# AMR3350.net
KiCad netlist of a schematic drawn in EAGLE
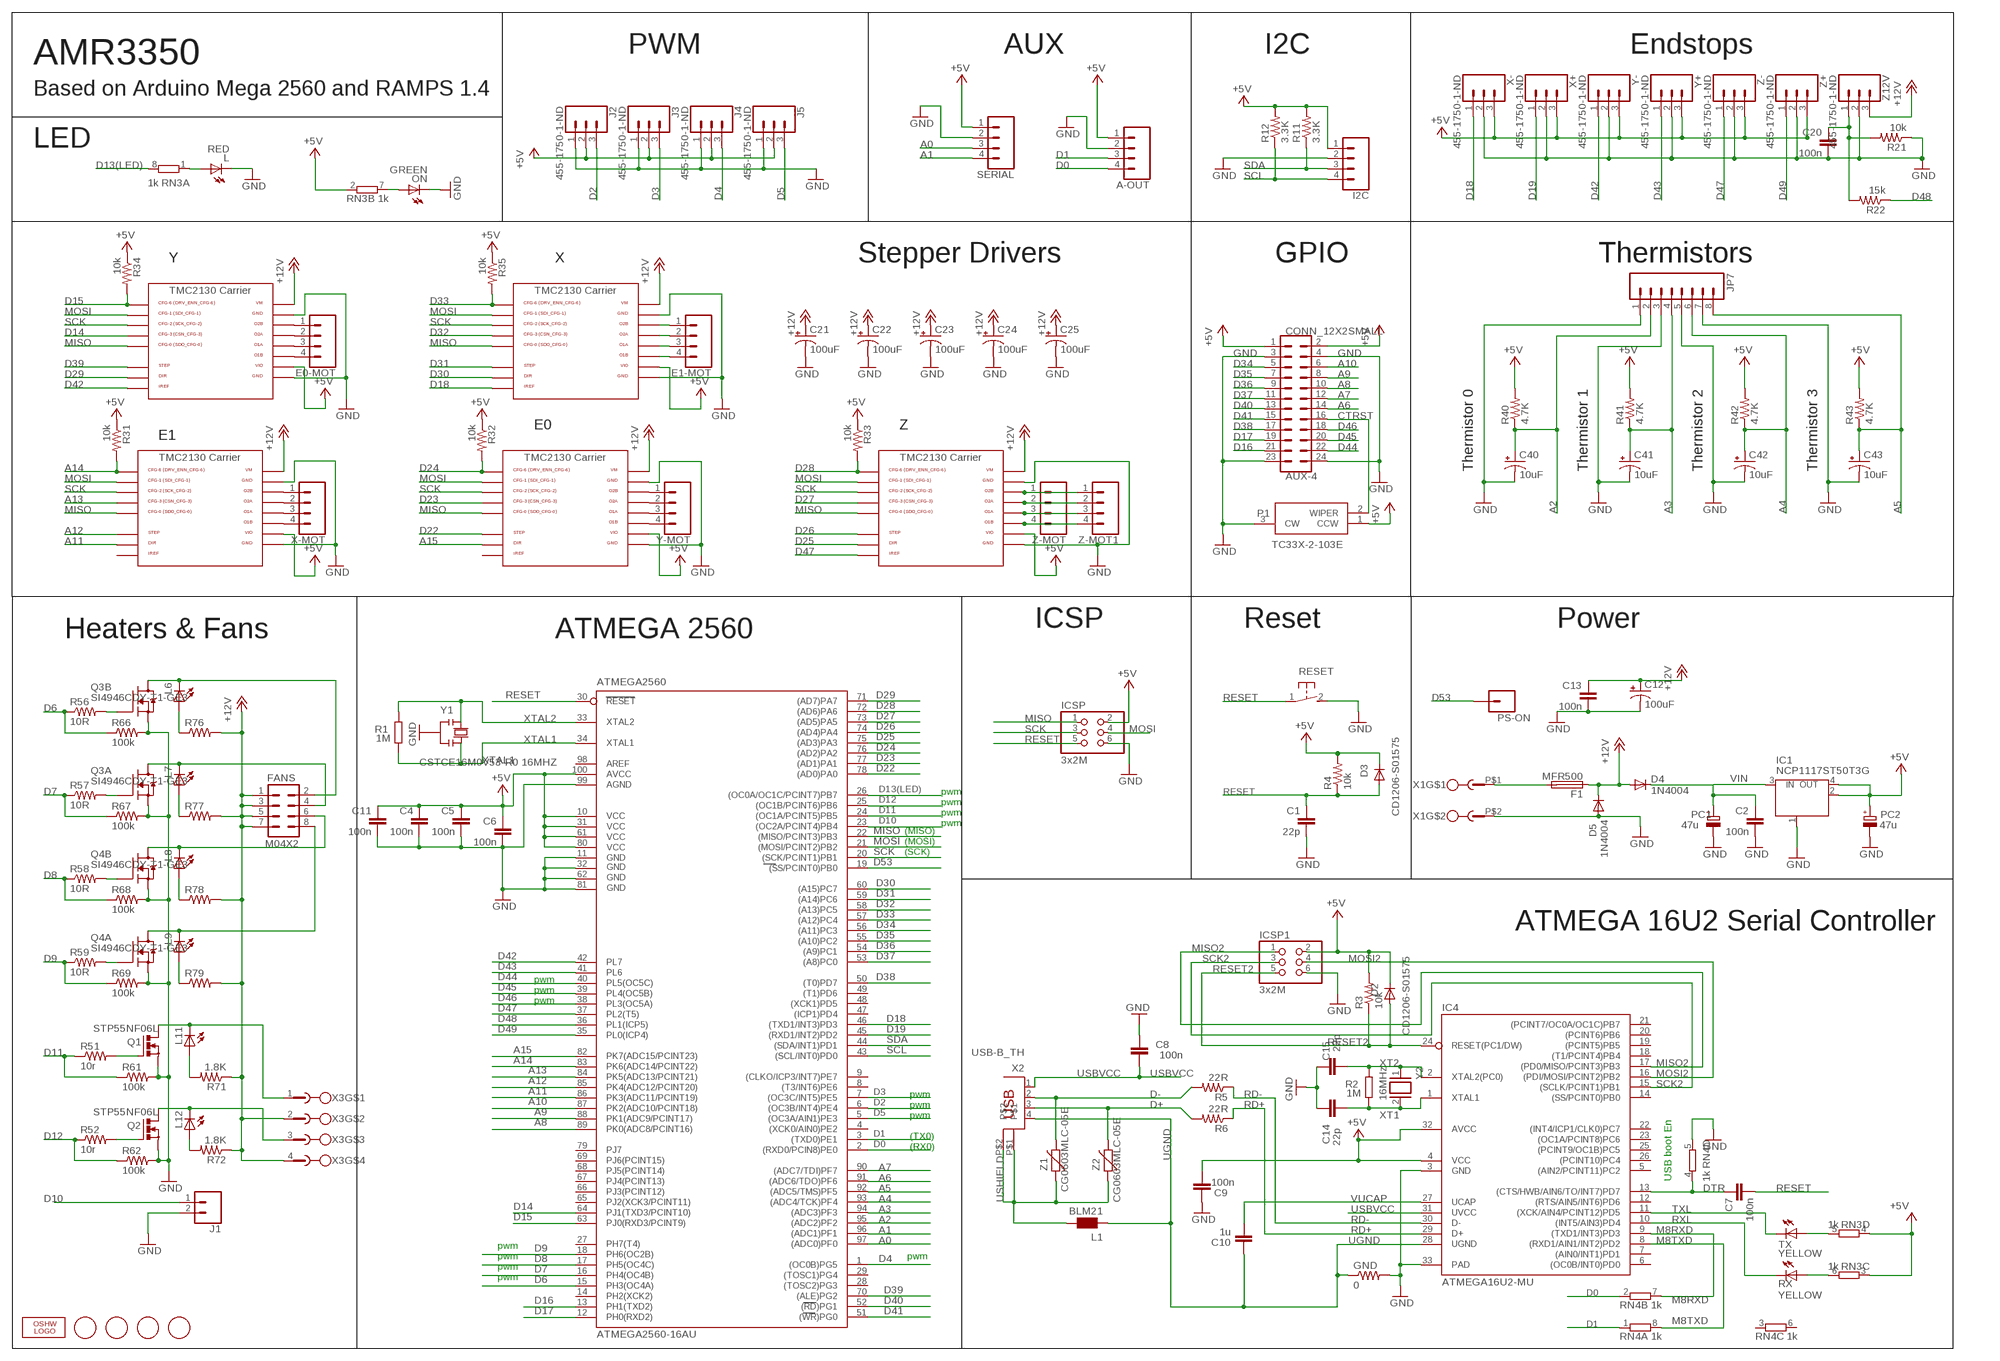
[diagram p0: schematic, sheet 1]

(export (version "E")
  (design (tool "Eeschema 10.0.6"))
  (components
    (comp (ref "A-OUT")
      (value "CONN_04SMALL")
      (footprint "eagle-import:1X04_SMALL")
      (libsource (lib "eagle-import") (part "CONN_04SMALL"))
    )
    (comp (ref "ATMEGA2560")
      (value "ATMEGA2560-16AU")
      (footprint "eagle-import:TQFP100")
      (libsource (lib "eagle-import") (part "ATMEGA2560AU2560-16"))
    )
    (comp (ref "AUX-4")
      (value "CONN_12X2SMALL")
      (footprint "eagle-import:2X12_SMALL")
      (libsource (lib "eagle-import") (part "CONN_12X2SMALL"))
    )
    (comp (ref "C1")
      (value "22p")
      (footprint "eagle-import:C0805RND")
      (libsource (lib "eagle-import") (part "C-EU"))
    )
    (comp (ref "C2")
      (value "100n")
      (footprint "eagle-import:C0805RND")
      (libsource (lib "eagle-import") (part "C-EU"))
    )
    (comp (ref "C4")
      (value "100n")
      (footprint "eagle-import:C0805RND")
      (libsource (lib "eagle-import") (part "C-EU"))
    )
    (comp (ref "C5")
      (value "100n")
      (footprint "eagle-import:C0805RND")
      (libsource (lib "eagle-import") (part "C-EU"))
    )
    (comp (ref "C6")
      (value "100n")
      (footprint "eagle-import:C0805RND")
      (libsource (lib "eagle-import") (part "C-EU"))
    )
    (comp (ref "C7")
      (value "100n")
      (footprint "eagle-import:C0805RND")
      (libsource (lib "eagle-import") (part "C-EU"))
    )
    (comp (ref "C8")
      (value "100n")
      (footprint "eagle-import:C0603-ROUND")
      (libsource (lib "eagle-import") (part "C-EU0603-RND"))
    )
    (comp (ref "C9")
      (value "100n")
      (footprint "eagle-import:C0603-ROUND")
      (libsource (lib "eagle-import") (part "C-EU0603-RND"))
    )
    (comp (ref "C10")
      (value "1u")
      (footprint "eagle-import:C0603-ROUND")
      (libsource (lib "eagle-import") (part "C-EU0603-RND"))
    )
    (comp (ref "C11")
      (value "100n")
      (footprint "eagle-import:C0603-ROUND")
      (libsource (lib "eagle-import") (part "C-EU0603-RND"))
    )
    (comp (ref "C12")
      (value "100uF")
      (footprint "eagle-import:153CLV-0605")
      (libsource (lib "eagle-import") (part "CPOL-US153CLV-0605"))
    )
    (comp (ref "C13")
      (value "100n")
      (footprint "eagle-import:C0805RND")
      (libsource (lib "eagle-import") (part "C-EU"))
    )
    (comp (ref "C14")
      (value "22p")
      (footprint "eagle-import:C0603-ROUND")
      (libsource (lib "eagle-import") (part "C-EU0603-RND"))
    )
    (comp (ref "C15")
      (value "22p")
      (footprint "eagle-import:C0603-ROUND")
      (libsource (lib "eagle-import") (part "C-EU0603-RND"))
    )
    (comp (ref "C20")
      (value "100n")
      (footprint "eagle-import:C0805RND")
      (libsource (lib "eagle-import") (part "C-EU"))
    )
    (comp (ref "C21")
      (value "100uF")
      (footprint "eagle-import:153CLV-0605")
      (libsource (lib "eagle-import") (part "CPOL-US153CLV-0605"))
    )
    (comp (ref "C22")
      (value "100uF")
      (footprint "eagle-import:153CLV-0605")
      (libsource (lib "eagle-import") (part "CPOL-US153CLV-0605"))
    )
    (comp (ref "C23")
      (value "100uF")
      (footprint "eagle-import:153CLV-0605")
      (libsource (lib "eagle-import") (part "CPOL-US153CLV-0605"))
    )
    (comp (ref "C24")
      (value "100uF")
      (footprint "eagle-import:153CLV-0605")
      (libsource (lib "eagle-import") (part "CPOL-US153CLV-0605"))
    )
    (comp (ref "C25")
      (value "100uF")
      (footprint "eagle-import:153CLV-0605")
      (libsource (lib "eagle-import") (part "CPOL-US153CLV-0605"))
    )
    (comp (ref "C40")
      (value "10uF")
      (footprint "eagle-import:153CLV-0405")
      (libsource (lib "eagle-import") (part "CPOL-US153CLV-0405"))
    )
    (comp (ref "C41")
      (value "10uF")
      (footprint "eagle-import:153CLV-0405")
      (libsource (lib "eagle-import") (part "CPOL-US153CLV-0405"))
    )
    (comp (ref "C42")
      (value "10uF")
      (footprint "eagle-import:153CLV-0405")
      (libsource (lib "eagle-import") (part "CPOL-US153CLV-0405"))
    )
    (comp (ref "C43")
      (value "10uF")
      (footprint "eagle-import:153CLV-0405")
      (libsource (lib "eagle-import") (part "CPOL-US153CLV-0405"))
    )
    (comp (ref "D2")
      (value "CD1206-S01575")
      (footprint "eagle-import:MINIMELF")
      (libsource (lib "eagle-import") (part "DIODE-MINIMELF"))
    )
    (comp (ref "D3")
      (value "CD1206-S01575")
      (footprint "eagle-import:MINIMELF")
      (libsource (lib "eagle-import") (part "DIODE-MINIMELF"))
    )
    (comp (ref "D4")
      (value "1N4004")
      (footprint "eagle-import:DO41-10")
      (libsource (lib "eagle-import") (part "1N4004"))
    )
    (comp (ref "D5")
      (value "1N4004")
      (footprint "eagle-import:DO41-10")
      (libsource (lib "eagle-import") (part "1N4004"))
    )
    (comp (ref "E0-MOT")
      (value "CONN_04SMALL")
      (footprint "eagle-import:1X04_SMALL")
      (libsource (lib "eagle-import") (part "CONN_04SMALL"))
    )
    (comp (ref "E1-MOT")
      (value "CONN_04SMALL")
      (footprint "eagle-import:1X04_SMALL")
      (libsource (lib "eagle-import") (part "CONN_04SMALL"))
    )
    (comp (ref "F1")
      (value "MFR500")
      (footprint "eagle-import:MFR500")
      (libsource (lib "eagle-import") (part "PTCFUSE"))
    )
    (comp (ref "FANS")
      (value "M04X2")
      (footprint "eagle-import:2X4")
      (libsource (lib "eagle-import") (part "M04X2"))
    )
    (comp (ref "FD1")
      (value "FIDUCIALMOUNT")
      (footprint "eagle-import:FIDUCIA-MOUNT")
      (libsource (lib "eagle-import") (part "FIDUCIALMOUNT"))
    )
    (comp (ref "FD2")
      (value "FIDUCIALMOUNT")
      (footprint "eagle-import:FIDUCIA-MOUNT")
      (libsource (lib "eagle-import") (part "FIDUCIALMOUNT"))
    )
    (comp (ref "FD3")
      (value "FIDUCIALMOUNT")
      (footprint "eagle-import:FIDUCIA-MOUNT")
      (libsource (lib "eagle-import") (part "FIDUCIALMOUNT"))
    )
    (comp (ref "FD4")
      (value "FIDUCIALMOUNT")
      (footprint "eagle-import:FIDUCIA-MOUNT")
      (libsource (lib "eagle-import") (part "FIDUCIALMOUNT"))
    )
    (comp (ref "GND")
      (value "0")
      (footprint "eagle-import:R0201")
      (libsource (lib "eagle-import") (part "R-US_R0201"))
    )
    (comp (ref "I2C")
      (value "CONN_04SMALL")
      (footprint "eagle-import:1X04_SMALL")
      (libsource (lib "eagle-import") (part "CONN_04SMALL"))
    )
    (comp (ref "IC1")
      (value "NCP1117ST50T3G")
      (footprint "eagle-import:SOT223")
      (libsource (lib "eagle-import") (part "MC33269ST-3.3T3"))
    )
    (comp (ref "IC4")
      (value "ATMEGA16U2-MU")
      (footprint "eagle-import:MLF32")
      (libsource (lib "eagle-import") (part "ATMEGA16U2-MU"))
    )
    (comp (ref "ICSP")
      (value "3x2M")
      (footprint "eagle-import:2X03")
      (libsource (lib "eagle-import") (part "PINHD-2X3"))
    )
    (comp (ref "ICSP1")
      (value "3x2M")
      (footprint "eagle-import:2X03")
      (libsource (lib "eagle-import") (part "PINHD-2X3"))
    )
    (comp (ref "J1")
      (value "CONN_02")
      (footprint "eagle-import:1X02")
      (libsource (lib "eagle-import") (part "CONN_02"))
    )
    (comp (ref "J2")
      (value "455-1750-1-ND")
      (footprint "eagle-import:1X03_SMALL")
      (libsource (lib "eagle-import") (part "CONN_03SMALL"))
    )
    (comp (ref "J3")
      (value "455-1750-1-ND")
      (footprint "eagle-import:1X03_SMALL")
      (libsource (lib "eagle-import") (part "CONN_03SMALL"))
    )
    (comp (ref "J4")
      (value "455-1750-1-ND")
      (footprint "eagle-import:1X03_SMALL")
      (libsource (lib "eagle-import") (part "CONN_03SMALL"))
    )
    (comp (ref "J5")
      (value "455-1750-1-ND")
      (footprint "eagle-import:1X03_SMALL")
      (libsource (lib "eagle-import") (part "CONN_03SMALL"))
    )
    (comp (ref "JP7")
      (value "CONN_08")
      (footprint "eagle-import:1X08_SMALL")
      (libsource (lib "eagle-import") (part "CONN_08"))
    )
    (comp (ref "L")
      (value "RED")
      (footprint "eagle-import:CHIP-LED0805")
      (libsource (lib "eagle-import") (part "LEDCHIP-LED0805"))
    )
    (comp (ref "L1")
      (value "BLM21")
      (footprint "eagle-import:0805")
      (libsource (lib "eagle-import") (part "WE-CBF_0805"))
    )
    (comp (ref "L6")
      (value "LEDCHIP-LED0603")
      (footprint "eagle-import:CHIP-LED0603")
      (libsource (lib "eagle-import") (part "LEDCHIP-LED0603"))
    )
    (comp (ref "L7")
      (value "LEDCHIP-LED0603")
      (footprint "eagle-import:CHIP-LED0603")
      (libsource (lib "eagle-import") (part "LEDCHIP-LED0603"))
    )
    (comp (ref "L8")
      (value "LEDCHIP-LED0603")
      (footprint "eagle-import:CHIP-LED0603")
      (libsource (lib "eagle-import") (part "LEDCHIP-LED0603"))
    )
    (comp (ref "L9")
      (value "LEDCHIP-LED0603")
      (footprint "eagle-import:CHIP-LED0603")
      (libsource (lib "eagle-import") (part "LEDCHIP-LED0603"))
    )
    (comp (ref "L11")
      (value "LEDCHIP-LED0805")
      (footprint "eagle-import:CHIP-LED0805")
      (libsource (lib "eagle-import") (part "LEDCHIP-LED0805"))
    )
    (comp (ref "L12")
      (value "LEDCHIP-LED0805")
      (footprint "eagle-import:CHIP-LED0805")
      (libsource (lib "eagle-import") (part "LEDCHIP-LED0805"))
    )
    (comp (ref "LOGO2")
      (value "OSHW_LOGO_6MILX0100-NT")
      (footprint "eagle-import:OSHW_6X100_NOTEXT")
      (libsource (lib "eagle-import") (part "OSHW_LOGO_6MILX0100-NT"))
    )
    (comp (ref "ON")
      (value "GREEN")
      (footprint "eagle-import:CHIP-LED0805")
      (libsource (lib "eagle-import") (part "LEDCHIP-LED0805"))
    )
    (comp (ref "P1")
      (value "TC33X-2-103E")
      (footprint "eagle-import:TC33X-2_1")
      (fields (field (name "RS_PART_NUMBER") "1673549"))
      (libsource (lib "eagle-import") (part "TC33X-2-103E"))
    )
    (comp (ref "PC1")
      (value "47u")
      (footprint "eagle-import:PANASONIC_D")
      (libsource (lib "eagle-import") (part "CPOL-EUD"))
    )
    (comp (ref "PC2")
      (value "47u")
      (footprint "eagle-import:PANASONIC_D")
      (libsource (lib "eagle-import") (part "CPOL-EUD"))
    )
    (comp (ref "PS-ON")
      (value "CONN_01SMALL")
      (footprint "eagle-import:1X01_SMALL")
      (libsource (lib "eagle-import") (part "CONN_01SMALL"))
    )
    (comp (ref "Q1")
      (value "STP55NF06L")
      (footprint "eagle-import:TO220BV")
      (libsource (lib "eagle-import") (part "IRF512"))
    )
    (comp (ref "Q2")
      (value "STP55NF06L")
      (footprint "eagle-import:TO220BV")
      (libsource (lib "eagle-import") (part "IRF512"))
    )
    (comp (ref "Q3")
      (value "SI4946CDY-T1-GE3")
      (footprint "eagle-import:SOIC127P600X175-8N")
      (libsource (lib "eagle-import") (part "SI4946CDY-T1-GE3"))
    )
    (comp (ref "Q4")
      (value "SI4946CDY-T1-GE3")
      (footprint "eagle-import:SOIC127P600X175-8N")
      (libsource (lib "eagle-import") (part "SI4946CDY-T1-GE3"))
    )
    (comp (ref "R1")
      (value "1M")
      (footprint "eagle-import:R0805RND")
      (libsource (lib "eagle-import") (part "R-EU_"))
    )
    (comp (ref "R2")
      (value "1M")
      (footprint "eagle-import:R0603-ROUND")
      (libsource (lib "eagle-import") (part "R-EU_R0603"))
    )
    (comp (ref "R3")
      (value "10k")
      (footprint "eagle-import:R0805")
      (libsource (lib "eagle-import") (part "resistor_348_R-US_R0805"))
    )
    (comp (ref "R4")
      (value "10k")
      (footprint "eagle-import:R0805")
      (libsource (lib "eagle-import") (part "resistor_348_R-US_R0805"))
    )
    (comp (ref "R5")
      (value "22R")
      (footprint "eagle-import:R0603")
      (libsource (lib "eagle-import") (part "resistor_348_R-US_R0603"))
    )
    (comp (ref "R6")
      (value "22R")
      (footprint "eagle-import:R0603")
      (libsource (lib "eagle-import") (part "resistor_348_R-US_R0603"))
    )
    (comp (ref "R11")
      (value "3.3K")
      (footprint "eagle-import:R0805")
      (libsource (lib "eagle-import") (part "R-US_R0805"))
    )
    (comp (ref "R12")
      (value "3.3K")
      (footprint "eagle-import:R0805")
      (libsource (lib "eagle-import") (part "R-US_R0805"))
    )
    (comp (ref "R21")
      (value "10k")
      (footprint "eagle-import:R0805")
      (libsource (lib "eagle-import") (part "R-US_R0805"))
    )
    (comp (ref "R22")
      (value "15k")
      (footprint "eagle-import:R0805")
      (libsource (lib "eagle-import") (part "R-US_R0805"))
    )
    (comp (ref "R31")
      (value "10k")
      (footprint "eagle-import:R0805")
      (libsource (lib "eagle-import") (part "R-US_R0805"))
    )
    (comp (ref "R32")
      (value "10k")
      (footprint "eagle-import:R0805")
      (libsource (lib "eagle-import") (part "R-US_R0805"))
    )
    (comp (ref "R33")
      (value "10k")
      (footprint "eagle-import:R0805")
      (libsource (lib "eagle-import") (part "R-US_R0805"))
    )
    (comp (ref "R34")
      (value "10k")
      (footprint "eagle-import:R0805")
      (libsource (lib "eagle-import") (part "R-US_R0805"))
    )
    (comp (ref "R35")
      (value "10k")
      (footprint "eagle-import:R0805")
      (libsource (lib "eagle-import") (part "R-US_R0805"))
    )
    (comp (ref "R40")
      (value "4.7K")
      (footprint "eagle-import:R0805")
      (libsource (lib "eagle-import") (part "R-US_R0805"))
    )
    (comp (ref "R41")
      (value "4.7K")
      (footprint "eagle-import:R0805")
      (libsource (lib "eagle-import") (part "R-US_R0805"))
    )
    (comp (ref "R42")
      (value "4.7K")
      (footprint "eagle-import:R0805")
      (libsource (lib "eagle-import") (part "R-US_R0805"))
    )
    (comp (ref "R43")
      (value "4.7K")
      (footprint "eagle-import:R0805")
      (libsource (lib "eagle-import") (part "R-US_R0805"))
    )
    (comp (ref "R51")
      (value "10r")
      (footprint "eagle-import:R0805")
      (libsource (lib "eagle-import") (part "resistor_R-US_R0805"))
    )
    (comp (ref "R52")
      (value "10r")
      (footprint "eagle-import:M0805")
      (libsource (lib "eagle-import") (part "resistor_R-US_M0805"))
    )
    (comp (ref "R56")
      (value "10R")
      (footprint "eagle-import:R0805")
      (libsource (lib "eagle-import") (part "resistor_348_R-US_R0805"))
    )
    (comp (ref "R57")
      (value "10R")
      (footprint "eagle-import:R0805")
      (libsource (lib "eagle-import") (part "resistor_348_R-US_R0805"))
    )
    (comp (ref "R58")
      (value "10R")
      (footprint "eagle-import:R0805")
      (libsource (lib "eagle-import") (part "resistor_348_R-US_R0805"))
    )
    (comp (ref "R59")
      (value "10R")
      (footprint "eagle-import:R0805")
      (libsource (lib "eagle-import") (part "resistor_348_R-US_R0805"))
    )
    (comp (ref "R61")
      (value "100k")
      (footprint "eagle-import:R0805")
      (libsource (lib "eagle-import") (part "R-US_R0805"))
    )
    (comp (ref "R62")
      (value "100k")
      (footprint "eagle-import:R0805")
      (libsource (lib "eagle-import") (part "R-US_R0805"))
    )
    (comp (ref "R66")
      (value "100k")
      (footprint "eagle-import:R0805")
      (libsource (lib "eagle-import") (part "resistor_348_R-US_R0805"))
    )
    (comp (ref "R67")
      (value "100k")
      (footprint "eagle-import:R0805")
      (libsource (lib "eagle-import") (part "resistor_348_R-US_R0805"))
    )
    (comp (ref "R68")
      (value "100k")
      (footprint "eagle-import:R0805")
      (libsource (lib "eagle-import") (part "resistor_348_R-US_R0805"))
    )
    (comp (ref "R69")
      (value "100k")
      (footprint "eagle-import:R0805")
      (libsource (lib "eagle-import") (part "resistor_348_R-US_R0805"))
    )
    (comp (ref "R71")
      (value "1.8K")
      (footprint "eagle-import:R0805")
      (libsource (lib "eagle-import") (part "R-US_R0805"))
    )
    (comp (ref "R72")
      (value "1.8K")
      (footprint "eagle-import:R0805")
      (libsource (lib "eagle-import") (part "R-US_R0805"))
    )
    (comp (ref "R76")
      (value "R-US_R0603")
      (footprint "eagle-import:R0603")
      (libsource (lib "eagle-import") (part "resistor_348_R-US_R0603"))
    )
    (comp (ref "R77")
      (value "R-US_R0603")
      (footprint "eagle-import:R0603")
      (libsource (lib "eagle-import") (part "resistor_348_R-US_R0603"))
    )
    (comp (ref "R78")
      (value "R-US_R0603")
      (footprint "eagle-import:R0603")
      (libsource (lib "eagle-import") (part "resistor_348_R-US_R0603"))
    )
    (comp (ref "R79")
      (value "R-US_R0603")
      (footprint "eagle-import:R0603")
      (libsource (lib "eagle-import") (part "resistor_348_R-US_R0603"))
    )
    (comp (ref "RESET")
      (value "31-XX")
      (footprint "eagle-import:B3F-31XX")
      (fields (field (name "MPN") "B3F-3100"))
      (libsource (lib "eagle-import") (part "31-XX"))
    )
    (comp (ref "RN3")
      (value "1k")
      (footprint "eagle-import:CAY16")
      (libsource (lib "eagle-import") (part "4R-NCAY16"))
    )
    (comp (ref "RN4")
      (value "1k")
      (footprint "eagle-import:CAY16")
      (libsource (lib "eagle-import") (part "4R-NCAY16"))
    )
    (comp (ref "RX")
      (value "YELLOW")
      (footprint "eagle-import:CHIP-LED0805")
      (libsource (lib "eagle-import") (part "LEDCHIP-LED0805"))
    )
    (comp (ref "SERIAL")
      (value "CONN_04SMALL")
      (footprint "eagle-import:1X04_SMALL")
      (libsource (lib "eagle-import") (part "CONN_04SMALL"))
    )
    (comp (ref "TX")
      (value "YELLOW")
      (footprint "eagle-import:CHIP-LED0805")
      (libsource (lib "eagle-import") (part "LEDCHIP-LED0805"))
    )
    (comp (ref "U$1")
      (value "TMC2130BREAKOUT")
      (footprint "eagle-import:TMC2130BREAKOUT")
      (libsource (lib "eagle-import") (part "TMC2130BREAKOUT"))
    )
    (comp (ref "U$2")
      (value "TMC2130BREAKOUT")
      (footprint "eagle-import:TMC2130BREAKOUT")
      (libsource (lib "eagle-import") (part "TMC2130BREAKOUT"))
    )
    (comp (ref "U$3")
      (value "TMC2130BREAKOUT")
      (footprint "eagle-import:TMC2130BREAKOUT")
      (libsource (lib "eagle-import") (part "TMC2130BREAKOUT"))
    )
    (comp (ref "U$4")
      (value "TMC2130BREAKOUT")
      (footprint "eagle-import:TMC2130BREAKOUT")
      (libsource (lib "eagle-import") (part "TMC2130BREAKOUT"))
    )
    (comp (ref "U$5")
      (value "TMC2130BREAKOUT")
      (footprint "eagle-import:TMC2130BREAKOUT")
      (libsource (lib "eagle-import") (part "TMC2130BREAKOUT"))
    )
    (comp (ref "X+")
      (value "455-1750-1-ND")
      (footprint "eagle-import:1X03_SMALL")
      (libsource (lib "eagle-import") (part "CONN_03SMALL"))
    )
    (comp (ref "X-")
      (value "455-1750-1-ND")
      (footprint "eagle-import:1X03_SMALL")
      (libsource (lib "eagle-import") (part "CONN_03SMALL"))
    )
    (comp (ref "X-MOT")
      (value "CONN_04SMALL")
      (footprint "eagle-import:1X04_SMALL")
      (libsource (lib "eagle-import") (part "CONN_04SMALL"))
    )
    (comp (ref "X1")
      (value "XT60")
      (footprint "eagle-import:XT60")
      (libsource (lib "eagle-import") (part "XT60"))
    )
    (comp (ref "X2")
      (value "USB-B_TH")
      (footprint "eagle-import:PN61729-NOSILK")
      (libsource (lib "eagle-import") (part "PN61729NOSILK"))
    )
    (comp (ref "X3")
      (value "4-PIN")
      (footprint "eagle-import:4-PIN")
      (libsource (lib "eagle-import") (part "4-PIN"))
    )
    (comp (ref "Y+")
      (value "455-1750-1-ND")
      (footprint "eagle-import:1X03_SMALL")
      (libsource (lib "eagle-import") (part "CONN_03SMALL"))
    )
    (comp (ref "Y-")
      (value "455-1750-1-ND")
      (footprint "eagle-import:1X03_SMALL")
      (libsource (lib "eagle-import") (part "CONN_03SMALL"))
    )
    (comp (ref "Y-MOT")
      (value "CONN_04SMALL")
      (footprint "eagle-import:1X04_SMALL")
      (libsource (lib "eagle-import") (part "CONN_04SMALL"))
    )
    (comp (ref "Y1")
      (value "CSTCE16M0V53-R0 16MHZ")
      (footprint "eagle-import:RESONATOR")
      (libsource (lib "eagle-import") (part "RESONATORMU"))
    )
    (comp (ref "Y2")
      (value "16MHz")
      (footprint "eagle-import:QS")
      (libsource (lib "eagle-import") (part "XTAL/S"))
    )
    (comp (ref "Z+")
      (value "455-1750-1-ND")
      (footprint "eagle-import:1X03_SMALL")
      (libsource (lib "eagle-import") (part "CONN_03SMALL"))
    )
    (comp (ref "Z-")
      (value "455-1750-1-ND")
      (footprint "eagle-import:1X03_SMALL")
      (libsource (lib "eagle-import") (part "CONN_03SMALL"))
    )
    (comp (ref "Z-MOT")
      (value "CONN_04SMALL")
      (footprint "eagle-import:1X04_SMALL")
      (libsource (lib "eagle-import") (part "CONN_04SMALL"))
    )
    (comp (ref "Z-MOT1")
      (value "CONN_04SMALL")
      (footprint "eagle-import:1X04_SMALL")
      (libsource (lib "eagle-import") (part "CONN_04SMALL"))
    )
    (comp (ref "Z1")
      (value "CG0603MLC-05E")
      (footprint "eagle-import:CT_CN0603")
      (libsource (lib "eagle-import") (part "VARISTORCN0603"))
    )
    (comp (ref "Z2")
      (value "CG0603MLC-05E")
      (footprint "eagle-import:CT_CN0603")
      (libsource (lib "eagle-import") (part "VARISTORCN0603"))
    )
    (comp (ref "Z12V")
      (value "455-1750-1-ND")
      (footprint "eagle-import:1X03_SMALL")
      (libsource (lib "eagle-import") (part "CONN_03SMALL"))
    )
  )
  (nets
    (net (code "1") (name "+5V") (class "Default")
      (node (ref "A-OUT") (pin "1") (pinfunction "1_1") (pintype "passive"))
      (node (ref "ATMEGA2560") (pin "10") (pinfunction "VCC_10") (pintype "power_in"))
      (node (ref "ATMEGA2560") (pin "100") (pinfunction "AVCC_100") (pintype "power_in"))
      (node (ref "ATMEGA2560") (pin "31") (pinfunction "VCC1_31") (pintype "power_in"))
      (node (ref "ATMEGA2560") (pin "61") (pinfunction "VCC2_61") (pintype "power_in"))
      (node (ref "ATMEGA2560") (pin "80") (pinfunction "VCC3_80") (pintype "power_in"))
      (node (ref "AUX-4") (pin "1") (pinfunction "1_1") (pintype "passive"))
      (node (ref "AUX-4") (pin "2") (pinfunction "2_2") (pintype "passive"))
      (node (ref "C11") (pin "1") (pinfunction "1_1") (pintype "passive"))
      (node (ref "C4") (pin "1") (pinfunction "1_1") (pintype "passive"))
      (node (ref "C5") (pin "1") (pinfunction "1_1") (pintype "passive"))
      (node (ref "C6") (pin "1") (pinfunction "1_1") (pintype "passive"))
      (node (ref "C9") (pin "1") (pinfunction "1_1") (pintype "passive"))
      (node (ref "D2") (pin "C") (pinfunction "C_C") (pintype "passive"))
      (node (ref "D3") (pin "C") (pinfunction "C_C") (pintype "passive"))
      (node (ref "I2C") (pin "1") (pinfunction "1_1") (pintype "passive"))
      (node (ref "IC1") (pin "2") (pinfunction "OUT_2") (pintype "passive"))
      (node (ref "IC1") (pin "4") (pinfunction "OUT_4") (pintype "passive"))
      (node (ref "IC4") (pin "32") (pinfunction "AVCC_32") (pintype "power_in"))
      (node (ref "IC4") (pin "4") (pinfunction "VCC_4") (pintype "power_in"))
      (node (ref "ICSP") (pin "2") (pinfunction "2_2") (pintype "passive"))
      (node (ref "ICSP1") (pin "2") (pinfunction "2_2") (pintype "passive"))
      (node (ref "J2") (pin "2") (pinfunction "2_2") (pintype "passive"))
      (node (ref "J3") (pin "2") (pinfunction "2_2") (pintype "passive"))
      (node (ref "J4") (pin "2") (pinfunction "2_2") (pintype "passive"))
      (node (ref "J5") (pin "2") (pinfunction "2_2") (pintype "passive"))
      (node (ref "P1") (pin "1") (pinfunction "CCW_1") (pintype "bidirectional"))
      (node (ref "PC2") (pin "+") (pinfunction "+_+") (pintype "passive"))
      (node (ref "R11") (pin "2") (pinfunction "2_2") (pintype "passive"))
      (node (ref "R12") (pin "2") (pinfunction "2_2") (pintype "passive"))
      (node (ref "R3") (pin "2") (pinfunction "2_2") (pintype "passive"))
      (node (ref "R31") (pin "1") (pinfunction "1_1") (pintype "passive"))
      (node (ref "R32") (pin "1") (pinfunction "1_1") (pintype "passive"))
      (node (ref "R33") (pin "1") (pinfunction "1_1") (pintype "passive"))
      (node (ref "R34") (pin "1") (pinfunction "1_1") (pintype "passive"))
      (node (ref "R35") (pin "1") (pinfunction "1_1") (pintype "passive"))
      (node (ref "R4") (pin "2") (pinfunction "2_2") (pintype "passive"))
      (node (ref "R40") (pin "2") (pinfunction "2_2") (pintype "passive"))
      (node (ref "R41") (pin "2") (pinfunction "2_2") (pintype "passive"))
      (node (ref "R42") (pin "2") (pinfunction "2_2") (pintype "passive"))
      (node (ref "R43") (pin "2") (pinfunction "2_2") (pintype "passive"))
      (node (ref "RN3") (pin "2") (pinfunction "1_2") (pintype "passive"))
      (node (ref "RN3") (pin "3") (pinfunction "1_3") (pintype "passive"))
      (node (ref "RN3") (pin "4") (pinfunction "1_4") (pintype "passive"))
      (node (ref "SERIAL") (pin "1") (pinfunction "1_1") (pintype "passive"))
      (node (ref "U$1") (pin "VIO") (pinfunction "VIO_VIO") (pintype "power_in"))
      (node (ref "U$2") (pin "VIO") (pinfunction "VIO_VIO") (pintype "power_in"))
      (node (ref "U$3") (pin "VIO") (pinfunction "VIO_VIO") (pintype "power_in"))
      (node (ref "U$4") (pin "VIO") (pinfunction "VIO_VIO") (pintype "power_in"))
      (node (ref "U$5") (pin "VIO") (pinfunction "VIO_VIO") (pintype "power_in"))
      (node (ref "X+") (pin "3") (pinfunction "3_3") (pintype "passive"))
      (node (ref "X-") (pin "3") (pinfunction "3_3") (pintype "passive"))
      (node (ref "Y+") (pin "3") (pinfunction "3_3") (pintype "passive"))
      (node (ref "Y-") (pin "3") (pinfunction "3_3") (pintype "passive"))
      (node (ref "Z+") (pin "3") (pinfunction "3_3") (pintype "passive"))
      (node (ref "Z-") (pin "3") (pinfunction "3_3") (pintype "passive"))
    )
    (net (code "2") (name "+12V") (class "Default")
      (node (ref "C12") (pin "+") (pinfunction "+_+") (pintype "passive"))
      (node (ref "C13") (pin "1") (pinfunction "1_1") (pintype "passive"))
      (node (ref "C21") (pin "+") (pinfunction "+_+") (pintype "passive"))
      (node (ref "C22") (pin "+") (pinfunction "+_+") (pintype "passive"))
      (node (ref "C23") (pin "+") (pinfunction "+_+") (pintype "passive"))
      (node (ref "C24") (pin "+") (pinfunction "+_+") (pintype "passive"))
      (node (ref "C25") (pin "+") (pinfunction "+_+") (pintype "passive"))
      (node (ref "D4") (pin "A") (pinfunction "A_A") (pintype "passive"))
      (node (ref "D5") (pin "C") (pinfunction "C_C") (pintype "passive"))
      (node (ref "F1") (pin "1") (pinfunction "1_1") (pintype "passive"))
      (node (ref "FANS") (pin "1") (pinfunction "1_1") (pintype "passive"))
      (node (ref "FANS") (pin "3") (pinfunction "3_3") (pintype "passive"))
      (node (ref "FANS") (pin "5") (pinfunction "5_5") (pintype "passive"))
      (node (ref "FANS") (pin "7") (pinfunction "7_7") (pintype "passive"))
      (node (ref "R71") (pin "1") (pinfunction "1_1") (pintype "passive"))
      (node (ref "R72") (pin "1") (pinfunction "1_1") (pintype "passive"))
      (node (ref "R76") (pin "2") (pinfunction "2_2") (pintype "passive"))
      (node (ref "R77") (pin "2") (pinfunction "2_2") (pintype "passive"))
      (node (ref "R78") (pin "2") (pinfunction "2_2") (pintype "passive"))
      (node (ref "R79") (pin "2") (pinfunction "2_2") (pintype "passive"))
      (node (ref "U$1") (pin "VM") (pinfunction "VM_VM") (pintype "power_in"))
      (node (ref "U$2") (pin "VM") (pinfunction "VM_VM") (pintype "power_in"))
      (node (ref "U$3") (pin "VM") (pinfunction "VM_VM") (pintype "power_in"))
      (node (ref "U$4") (pin "VM") (pinfunction "VM_VM") (pintype "power_in"))
      (node (ref "U$5") (pin "VM") (pinfunction "VM_VM") (pintype "power_in"))
      (node (ref "X3") (pin "2") (pinfunction "1_2") (pintype "passive"))
      (node (ref "X3") (pin "4") (pinfunction "1_4") (pintype "passive"))
      (node (ref "Z12V") (pin "3") (pinfunction "3_3") (pintype "passive"))
    )
    (net (code "3") (name "/A0") (class "Default")
      (node (ref "ATMEGA2560") (pin "97") (pinfunction "(ADC0)PF0_97") (pintype "bidirectional"))
      (node (ref "SERIAL") (pin "3") (pinfunction "3_3") (pintype "passive"))
    )
    (net (code "4") (name "/A1") (class "Default")
      (node (ref "ATMEGA2560") (pin "96") (pinfunction "(ADC1)PF1_96") (pintype "bidirectional"))
      (node (ref "SERIAL") (pin "4") (pinfunction "4_4") (pintype "passive"))
    )
    (net (code "5") (name "/A2") (class "Default")
      (node (ref "ATMEGA2560") (pin "95") (pinfunction "(ADC2)PF2_95") (pintype "bidirectional"))
      (node (ref "C40") (pin "+") (pinfunction "+_+") (pintype "passive"))
      (node (ref "JP7") (pin "2") (pinfunction "2_2") (pintype "passive"))
      (node (ref "R40") (pin "1") (pinfunction "1_1") (pintype "passive"))
    )
    (net (code "6") (name "/A3") (class "Default")
      (node (ref "ATMEGA2560") (pin "94") (pinfunction "(ADC3)PF3_94") (pintype "bidirectional"))
      (node (ref "C41") (pin "+") (pinfunction "+_+") (pintype "passive"))
      (node (ref "JP7") (pin "4") (pinfunction "4_4") (pintype "passive"))
      (node (ref "R41") (pin "1") (pinfunction "1_1") (pintype "passive"))
    )
    (net (code "7") (name "/A4") (class "Default")
      (node (ref "ATMEGA2560") (pin "93") (pinfunction "(ADC4/TCK)PF4_93") (pintype "bidirectional"))
      (node (ref "C42") (pin "+") (pinfunction "+_+") (pintype "passive"))
      (node (ref "JP7") (pin "6") (pinfunction "6_6") (pintype "passive"))
      (node (ref "R42") (pin "1") (pinfunction "1_1") (pintype "passive"))
    )
    (net (code "8") (name "/A5") (class "Default")
      (node (ref "ATMEGA2560") (pin "92") (pinfunction "(ADC5/TMS)PF5_92") (pintype "bidirectional"))
      (node (ref "C43") (pin "+") (pinfunction "+_+") (pintype "passive"))
      (node (ref "JP7") (pin "8") (pinfunction "8_8") (pintype "passive"))
      (node (ref "R43") (pin "1") (pinfunction "1_1") (pintype "passive"))
    )
    (net (code "9") (name "/A6") (class "Default")
      (node (ref "ATMEGA2560") (pin "91") (pinfunction "(ADC6/TDO)PF6_91") (pintype "bidirectional"))
      (node (ref "AUX-4") (pin "14") (pinfunction "14_14") (pintype "passive"))
    )
    (net (code "10") (name "/A7") (class "Default")
      (node (ref "ATMEGA2560") (pin "90") (pinfunction "(ADC7/TDI)PF7_90") (pintype "bidirectional"))
      (node (ref "AUX-4") (pin "12") (pinfunction "12_12") (pintype "passive"))
    )
    (net (code "11") (name "/A8") (class "Default")
      (node (ref "ATMEGA2560") (pin "89") (pinfunction "PK0(ADC8/PCINT16)_89") (pintype "bidirectional"))
      (node (ref "AUX-4") (pin "10") (pinfunction "10_10") (pintype "passive"))
    )
    (net (code "12") (name "/A9") (class "Default")
      (node (ref "ATMEGA2560") (pin "88") (pinfunction "PK1(ADC9/PCINT17)_88") (pintype "bidirectional"))
      (node (ref "AUX-4") (pin "8") (pinfunction "8_8") (pintype "passive"))
    )
    (net (code "13") (name "/A10") (class "Default")
      (node (ref "ATMEGA2560") (pin "87") (pinfunction "PK2(ADC10/PCINT18)_87") (pintype "bidirectional"))
      (node (ref "AUX-4") (pin "6") (pinfunction "6_6") (pintype "passive"))
    )
    (net (code "14") (name "/A11") (class "Default")
      (node (ref "ATMEGA2560") (pin "86") (pinfunction "PK3(ADC11/PCINT19)_86") (pintype "bidirectional"))
      (node (ref "U$1") (pin "DIR") (pinfunction "DIR_DIR") (pintype "input"))
    )
    (net (code "15") (name "/A12") (class "Default")
      (node (ref "ATMEGA2560") (pin "85") (pinfunction "PK4(ADC12/PCINT20)_85") (pintype "bidirectional"))
      (node (ref "U$1") (pin "STEP") (pinfunction "STEP_STEP") (pintype "input"))
    )
    (net (code "16") (name "/A13") (class "Default")
      (node (ref "ATMEGA2560") (pin "84") (pinfunction "PK5(ADC13/PCINT21)_84") (pintype "bidirectional"))
      (node (ref "U$1") (pin "CFG-3") (pinfunction "CFG-3_CFG-3") (pintype "bidirectional"))
    )
    (net (code "17") (name "/A14") (class "Default")
      (node (ref "ATMEGA2560") (pin "83") (pinfunction "PK6(ADC14/PCINT22)_83") (pintype "bidirectional"))
      (node (ref "R31") (pin "2") (pinfunction "2_2") (pintype "passive"))
      (node (ref "U$1") (pin "CFG-6") (pinfunction "CFG-6_CFG-6") (pintype "bidirectional"))
    )
    (net (code "18") (name "/A15") (class "Default")
      (node (ref "ATMEGA2560") (pin "82") (pinfunction "PK7(ADC15/PCINT23)_82") (pintype "bidirectional"))
      (node (ref "U$2") (pin "DIR") (pinfunction "DIR_DIR") (pintype "input"))
    )
    (net (code "19") (name "/CTRST") (class "Default")
      (node (ref "AUX-4") (pin "16") (pinfunction "16_16") (pintype "passive"))
      (node (ref "P1") (pin "2") (pinfunction "WIPER_2") (pintype "bidirectional"))
    )
    (net (code "20") (name "/D+") (class "Default")
      (node (ref "R6") (pin "2") (pinfunction "2_2") (pintype "passive"))
      (node (ref "X2") (pin "3") (pinfunction "3_3") (pintype "bidirectional"))
      (node (ref "Z2") (pin "2") (pinfunction "2_2") (pintype "passive"))
    )
    (net (code "21") (name "/D-") (class "Default")
      (node (ref "R5") (pin "2") (pinfunction "2_2") (pintype "passive"))
      (node (ref "X2") (pin "2") (pinfunction "2_2") (pintype "bidirectional"))
      (node (ref "Z1") (pin "2") (pinfunction "2_2") (pintype "passive"))
    )
    (net (code "22") (name "/D0") (class "Default")
      (node (ref "A-OUT") (pin "4") (pinfunction "4_4") (pintype "passive"))
      (node (ref "ATMEGA2560") (pin "2") (pinfunction "(RXD0/PCIN8)PE0_2") (pintype "bidirectional"))
      (node (ref "RN4") (pin "2") (pinfunction "1_2") (pintype "passive"))
    )
    (net (code "23") (name "/D1") (class "Default")
      (node (ref "A-OUT") (pin "3") (pinfunction "3_3") (pintype "passive"))
      (node (ref "ATMEGA2560") (pin "3") (pinfunction "(TXD0)PE1_3") (pintype "bidirectional"))
      (node (ref "RN4") (pin "1") (pinfunction "1_1") (pintype "passive"))
    )
    (net (code "24") (name "/D2") (class "Default")
      (node (ref "ATMEGA2560") (pin "6") (pinfunction "(OC3B/INT4)PE4_6") (pintype "bidirectional"))
      (node (ref "J2") (pin "3") (pinfunction "3_3") (pintype "passive"))
    )
    (net (code "25") (name "/D3") (class "Default")
      (node (ref "ATMEGA2560") (pin "7") (pinfunction "(OC3C/INT5)PE5_7") (pintype "bidirectional"))
      (node (ref "J3") (pin "3") (pinfunction "3_3") (pintype "passive"))
    )
    (net (code "26") (name "/D4") (class "Default")
      (node (ref "ATMEGA2560") (pin "1") (pinfunction "(OC0B)PG5_1") (pintype "bidirectional"))
      (node (ref "J4") (pin "3") (pinfunction "3_3") (pintype "passive"))
    )
    (net (code "27") (name "/D5") (class "Default")
      (node (ref "ATMEGA2560") (pin "5") (pinfunction "(OC3A/AIN1)PE3_5") (pintype "bidirectional"))
      (node (ref "J5") (pin "3") (pinfunction "3_3") (pintype "passive"))
    )
    (net (code "28") (name "/D6") (class "Default")
      (node (ref "ATMEGA2560") (pin "15") (pinfunction "PH3(OC4A)_15") (pintype "bidirectional"))
      (node (ref "R56") (pin "1") (pinfunction "1_1") (pintype "passive"))
      (node (ref "R66") (pin "1") (pinfunction "1_1") (pintype "passive"))
    )
    (net (code "29") (name "/D7") (class "Default")
      (node (ref "ATMEGA2560") (pin "16") (pinfunction "PH4(OC4B)_16") (pintype "bidirectional"))
      (node (ref "R57") (pin "1") (pinfunction "1_1") (pintype "passive"))
      (node (ref "R67") (pin "1") (pinfunction "1_1") (pintype "passive"))
    )
    (net (code "30") (name "/D8") (class "Default")
      (node (ref "ATMEGA2560") (pin "17") (pinfunction "PH5(OC4C)_17") (pintype "bidirectional"))
      (node (ref "R58") (pin "1") (pinfunction "1_1") (pintype "passive"))
      (node (ref "R68") (pin "1") (pinfunction "1_1") (pintype "passive"))
    )
    (net (code "31") (name "/D9") (class "Default")
      (node (ref "ATMEGA2560") (pin "18") (pinfunction "PH6(OC2B)_18") (pintype "bidirectional"))
      (node (ref "R59") (pin "1") (pinfunction "1_1") (pintype "passive"))
      (node (ref "R69") (pin "1") (pinfunction "1_1") (pintype "passive"))
    )
    (net (code "32") (name "/D10") (class "Default")
      (node (ref "ATMEGA2560") (pin "23") (pinfunction "(OC2A/PCINT4)PB4_23") (pintype "bidirectional"))
      (node (ref "J1") (pin "1") (pinfunction "1_1") (pintype "passive"))
    )
    (net (code "33") (name "/D11") (class "Default")
      (node (ref "ATMEGA2560") (pin "24") (pinfunction "(OC1A/PCINT5)PB5_24") (pintype "bidirectional"))
      (node (ref "R51") (pin "1") (pinfunction "1_1") (pintype "passive"))
      (node (ref "R61") (pin "1") (pinfunction "1_1") (pintype "passive"))
    )
    (net (code "34") (name "/D12") (class "Default")
      (node (ref "ATMEGA2560") (pin "25") (pinfunction "(OC1B/PCINT6)PB6_25") (pintype "bidirectional"))
      (node (ref "R52") (pin "1") (pinfunction "1_1") (pintype "passive"))
      (node (ref "R62") (pin "1") (pinfunction "1_1") (pintype "passive"))
    )
    (net (code "35") (name "/D13(LED)") (class "Default")
      (node (ref "ATMEGA2560") (pin "26") (pinfunction "(OC0A/OC1C/PCINT7)PB7_26") (pintype "bidirectional"))
      (node (ref "RN3") (pin "8") (pinfunction "2_8") (pintype "passive"))
    )
    (net (code "36") (name "/D14") (class "Default")
      (node (ref "ATMEGA2560") (pin "64") (pinfunction "PJ1(TXD3/PCINT10)_64") (pintype "bidirectional"))
      (node (ref "U$5") (pin "CFG-3") (pinfunction "CFG-3_CFG-3") (pintype "bidirectional"))
    )
    (net (code "37") (name "/D15") (class "Default")
      (node (ref "ATMEGA2560") (pin "63") (pinfunction "PJ0(RXD3/PCINT9)_63") (pintype "bidirectional"))
      (node (ref "R34") (pin "2") (pinfunction "2_2") (pintype "passive"))
      (node (ref "U$5") (pin "CFG-6") (pinfunction "CFG-6_CFG-6") (pintype "bidirectional"))
    )
    (net (code "38") (name "/D16") (class "Default")
      (node (ref "ATMEGA2560") (pin "13") (pinfunction "PH1(TXD2)_13") (pintype "bidirectional"))
      (node (ref "AUX-4") (pin "21") (pinfunction "21_21") (pintype "passive"))
    )
    (net (code "39") (name "/D17") (class "Default")
      (node (ref "ATMEGA2560") (pin "12") (pinfunction "PH0(RXD2)_12") (pintype "bidirectional"))
      (node (ref "AUX-4") (pin "19") (pinfunction "19_19") (pintype "passive"))
    )
    (net (code "40") (name "/D18") (class "Default")
      (node (ref "ATMEGA2560") (pin "46") (pinfunction "(TXD1/INT3)PD3_46") (pintype "bidirectional"))
      (node (ref "U$4") (pin "IREF") (pinfunction "IREF_IREF") (pintype "bidirectional"))
      (node (ref "X-") (pin "1") (pinfunction "1_1") (pintype "passive"))
    )
    (net (code "41") (name "/D19") (class "Default")
      (node (ref "ATMEGA2560") (pin "45") (pinfunction "(RXD1/INT2)PD2_45") (pintype "bidirectional"))
      (node (ref "X+") (pin "1") (pinfunction "1_1") (pintype "passive"))
    )
    (net (code "42") (name "/D22") (class "Default")
      (node (ref "ATMEGA2560") (pin "78") (pinfunction "(AD0)PA0_78") (pintype "bidirectional"))
      (node (ref "U$2") (pin "STEP") (pinfunction "STEP_STEP") (pintype "input"))
    )
    (net (code "43") (name "/D23") (class "Default")
      (node (ref "ATMEGA2560") (pin "77") (pinfunction "(AD1)PA1_77") (pintype "bidirectional"))
      (node (ref "U$2") (pin "CFG-3") (pinfunction "CFG-3_CFG-3") (pintype "bidirectional"))
    )
    (net (code "44") (name "/D24") (class "Default")
      (node (ref "ATMEGA2560") (pin "76") (pinfunction "(AD2)PA2_76") (pintype "bidirectional"))
      (node (ref "R32") (pin "2") (pinfunction "2_2") (pintype "passive"))
      (node (ref "U$2") (pin "CFG-6") (pinfunction "CFG-6_CFG-6") (pintype "bidirectional"))
    )
    (net (code "45") (name "/D25") (class "Default")
      (node (ref "ATMEGA2560") (pin "75") (pinfunction "(AD3)PA3_75") (pintype "bidirectional"))
      (node (ref "U$3") (pin "DIR") (pinfunction "DIR_DIR") (pintype "input"))
    )
    (net (code "46") (name "/D26") (class "Default")
      (node (ref "ATMEGA2560") (pin "74") (pinfunction "(AD4)PA4_74") (pintype "bidirectional"))
      (node (ref "U$3") (pin "STEP") (pinfunction "STEP_STEP") (pintype "input"))
    )
    (net (code "47") (name "/D27") (class "Default")
      (node (ref "ATMEGA2560") (pin "73") (pinfunction "(AD5)PA5_73") (pintype "bidirectional"))
      (node (ref "U$3") (pin "CFG-3") (pinfunction "CFG-3_CFG-3") (pintype "bidirectional"))
    )
    (net (code "48") (name "/D28") (class "Default")
      (node (ref "ATMEGA2560") (pin "72") (pinfunction "(AD6)PA6_72") (pintype "bidirectional"))
      (node (ref "R33") (pin "2") (pinfunction "2_2") (pintype "passive"))
      (node (ref "U$3") (pin "CFG-6") (pinfunction "CFG-6_CFG-6") (pintype "bidirectional"))
    )
    (net (code "49") (name "/D29") (class "Default")
      (node (ref "ATMEGA2560") (pin "71") (pinfunction "(AD7)PA7_71") (pintype "bidirectional"))
      (node (ref "U$5") (pin "DIR") (pinfunction "DIR_DIR") (pintype "input"))
    )
    (net (code "50") (name "/D30") (class "Default")
      (node (ref "ATMEGA2560") (pin "60") (pinfunction "(A15)PC7_60") (pintype "bidirectional"))
      (node (ref "U$4") (pin "DIR") (pinfunction "DIR_DIR") (pintype "input"))
    )
    (net (code "51") (name "/D31") (class "Default")
      (node (ref "ATMEGA2560") (pin "59") (pinfunction "(A14)PC6_59") (pintype "bidirectional"))
      (node (ref "U$4") (pin "STEP") (pinfunction "STEP_STEP") (pintype "input"))
    )
    (net (code "52") (name "/D32") (class "Default")
      (node (ref "ATMEGA2560") (pin "58") (pinfunction "(A13)PC5_58") (pintype "bidirectional"))
      (node (ref "U$4") (pin "CFG-3") (pinfunction "CFG-3_CFG-3") (pintype "bidirectional"))
    )
    (net (code "53") (name "/D33") (class "Default")
      (node (ref "ATMEGA2560") (pin "57") (pinfunction "(A12)PC4_57") (pintype "bidirectional"))
      (node (ref "R35") (pin "2") (pinfunction "2_2") (pintype "passive"))
      (node (ref "U$4") (pin "CFG-6") (pinfunction "CFG-6_CFG-6") (pintype "bidirectional"))
    )
    (net (code "54") (name "/D34") (class "Default")
      (node (ref "ATMEGA2560") (pin "56") (pinfunction "(A11)PC3_56") (pintype "bidirectional"))
      (node (ref "AUX-4") (pin "5") (pinfunction "5_5") (pintype "passive"))
    )
    (net (code "55") (name "/D35") (class "Default")
      (node (ref "ATMEGA2560") (pin "55") (pinfunction "(A10)PC2_55") (pintype "bidirectional"))
      (node (ref "AUX-4") (pin "7") (pinfunction "7_7") (pintype "passive"))
    )
    (net (code "56") (name "/D36") (class "Default")
      (node (ref "ATMEGA2560") (pin "54") (pinfunction "(A9)PC1_54") (pintype "bidirectional"))
      (node (ref "AUX-4") (pin "9") (pinfunction "9_9") (pintype "passive"))
    )
    (net (code "57") (name "/D37") (class "Default")
      (node (ref "ATMEGA2560") (pin "53") (pinfunction "(A8)PC0_53") (pintype "bidirectional"))
      (node (ref "AUX-4") (pin "11") (pinfunction "11_11") (pintype "passive"))
    )
    (net (code "58") (name "/D38") (class "Default")
      (node (ref "ATMEGA2560") (pin "50") (pinfunction "(T0)PD7_50") (pintype "bidirectional"))
      (node (ref "AUX-4") (pin "17") (pinfunction "17_17") (pintype "passive"))
    )
    (net (code "59") (name "/D39") (class "Default")
      (node (ref "ATMEGA2560") (pin "70") (pinfunction "(ALE)PG2_70") (pintype "bidirectional"))
      (node (ref "U$5") (pin "STEP") (pinfunction "STEP_STEP") (pintype "input"))
    )
    (net (code "60") (name "/D40") (class "Default")
      (node (ref "ATMEGA2560") (pin "52") (pinfunction "(RD)PG1_52") (pintype "bidirectional"))
      (node (ref "AUX-4") (pin "13") (pinfunction "13_13") (pintype "passive"))
    )
    (net (code "61") (name "/D41") (class "Default")
      (node (ref "ATMEGA2560") (pin "51") (pinfunction "(WR)PG0_51") (pintype "bidirectional"))
      (node (ref "AUX-4") (pin "15") (pinfunction "15_15") (pintype "passive"))
    )
    (net (code "62") (name "/D42") (class "Default")
      (node (ref "ATMEGA2560") (pin "42") (pinfunction "PL7_42") (pintype "bidirectional"))
      (node (ref "U$5") (pin "IREF") (pinfunction "IREF_IREF") (pintype "bidirectional"))
      (node (ref "Y-") (pin "1") (pinfunction "1_1") (pintype "passive"))
    )
    (net (code "63") (name "/D43") (class "Default")
      (node (ref "ATMEGA2560") (pin "41") (pinfunction "PL6_41") (pintype "bidirectional"))
      (node (ref "Y+") (pin "1") (pinfunction "1_1") (pintype "passive"))
    )
    (net (code "64") (name "/D44") (class "Default")
      (node (ref "ATMEGA2560") (pin "40") (pinfunction "PL5(OC5C)_40") (pintype "bidirectional"))
      (node (ref "AUX-4") (pin "22") (pinfunction "22_22") (pintype "passive"))
    )
    (net (code "65") (name "/D45") (class "Default")
      (node (ref "ATMEGA2560") (pin "39") (pinfunction "PL4(OC5B)_39") (pintype "bidirectional"))
      (node (ref "AUX-4") (pin "20") (pinfunction "20_20") (pintype "passive"))
    )
    (net (code "66") (name "/D46") (class "Default")
      (node (ref "ATMEGA2560") (pin "38") (pinfunction "PL3(OC5A)_38") (pintype "bidirectional"))
      (node (ref "AUX-4") (pin "18") (pinfunction "18_18") (pintype "passive"))
    )
    (net (code "67") (name "/D47") (class "Default")
      (node (ref "ATMEGA2560") (pin "37") (pinfunction "PL2(T5)_37") (pintype "bidirectional"))
      (node (ref "U$3") (pin "IREF") (pinfunction "IREF_IREF") (pintype "bidirectional"))
      (node (ref "Z-") (pin "1") (pinfunction "1_1") (pintype "passive"))
    )
    (net (code "68") (name "/D48") (class "Default")
      (node (ref "ATMEGA2560") (pin "36") (pinfunction "PL1(ICP5)_36") (pintype "bidirectional"))
      (node (ref "R22") (pin "1") (pinfunction "1_1") (pintype "passive"))
    )
    (net (code "69") (name "/D49") (class "Default")
      (node (ref "ATMEGA2560") (pin "35") (pinfunction "PL0(ICP4)_35") (pintype "bidirectional"))
      (node (ref "Z+") (pin "1") (pinfunction "1_1") (pintype "passive"))
    )
    (net (code "70") (name "/D53") (class "Default")
      (node (ref "ATMEGA2560") (pin "19") (pinfunction "(SS/PCINT0)PB0_19") (pintype "bidirectional"))
      (node (ref "PS-ON") (pin "1") (pinfunction "1_1") (pintype "passive"))
    )
    (net (code "71") (name "/DTR") (class "Default")
      (node (ref "C7") (pin "1") (pinfunction "1_1") (pintype "passive"))
      (node (ref "IC4") (pin "13") (pinfunction "(CTS/HWB/AIN6/TO/INT7)PD7_13") (pintype "bidirectional"))
      (node (ref "RN4") (pin "4") (pinfunction "1_4") (pintype "passive"))
    )
    (net (code "72") (name "/M8RXD") (class "Default")
      (node (ref "IC4") (pin "9") (pinfunction "(TXD1/INT3)PD3_9") (pintype "bidirectional"))
      (node (ref "RN4") (pin "7") (pinfunction "2_7") (pintype "passive"))
    )
    (net (code "73") (name "/M8TXD") (class "Default")
      (node (ref "IC4") (pin "8") (pinfunction "(RXD1/AIN1/INT2)PD2_8") (pintype "bidirectional"))
      (node (ref "RN4") (pin "8") (pinfunction "2_8") (pintype "passive"))
    )
    (net (code "74") (name "/MISO") (class "Default")
      (node (ref "ATMEGA2560") (pin "22") (pinfunction "(MISO/PCINT3)PB3_22") (pintype "bidirectional"))
      (node (ref "ICSP") (pin "1") (pinfunction "1_1") (pintype "passive"))
      (node (ref "U$1") (pin "CFG-0") (pinfunction "CFG-0_CFG-0") (pintype "bidirectional"))
      (node (ref "U$2") (pin "CFG-0") (pinfunction "CFG-0_CFG-0") (pintype "bidirectional"))
      (node (ref "U$3") (pin "CFG-0") (pinfunction "CFG-0_CFG-0") (pintype "bidirectional"))
      (node (ref "U$4") (pin "CFG-0") (pinfunction "CFG-0_CFG-0") (pintype "bidirectional"))
      (node (ref "U$5") (pin "CFG-0") (pinfunction "CFG-0_CFG-0") (pintype "bidirectional"))
    )
    (net (code "75") (name "/MISO2") (class "Default")
      (node (ref "IC4") (pin "17") (pinfunction "(PD0/MISO/PCINT3)PB3_17") (pintype "bidirectional"))
      (node (ref "ICSP1") (pin "1") (pinfunction "1_1") (pintype "passive"))
    )
    (net (code "76") (name "/MOSI") (class "Default")
      (node (ref "ATMEGA2560") (pin "21") (pinfunction "(MOSI/PCINT2)PB2_21") (pintype "bidirectional"))
      (node (ref "ICSP") (pin "4") (pinfunction "4_4") (pintype "passive"))
      (node (ref "U$1") (pin "CFG-1") (pinfunction "CFG-1_CFG-1") (pintype "bidirectional"))
      (node (ref "U$2") (pin "CFG-1") (pinfunction "CFG-1_CFG-1") (pintype "bidirectional"))
      (node (ref "U$3") (pin "CFG-1") (pinfunction "CFG-1_CFG-1") (pintype "bidirectional"))
      (node (ref "U$4") (pin "CFG-1") (pinfunction "CFG-1_CFG-1") (pintype "bidirectional"))
      (node (ref "U$5") (pin "CFG-1") (pinfunction "CFG-1_CFG-1") (pintype "bidirectional"))
    )
    (net (code "77") (name "/MOSI2") (class "Default")
      (node (ref "IC4") (pin "16") (pinfunction "(PDI/MOSI/PCINT2)PB2_16") (pintype "bidirectional"))
      (node (ref "ICSP1") (pin "4") (pinfunction "4_4") (pintype "passive"))
    )
    (net (code "78") (name "/RD+") (class "Default")
      (node (ref "IC4") (pin "29") (pinfunction "D+_29") (pintype "bidirectional"))
      (node (ref "R6") (pin "1") (pinfunction "1_1") (pintype "passive"))
    )
    (net (code "79") (name "/RD-") (class "Default")
      (node (ref "IC4") (pin "30") (pinfunction "D-_30") (pintype "bidirectional"))
      (node (ref "R5") (pin "1") (pinfunction "1_1") (pintype "passive"))
    )
    (net (code "80") (name "/RESET") (class "Default")
      (node (ref "ATMEGA2560") (pin "30") (pinfunction "RESET_30") (pintype "input"))
      (node (ref "C1") (pin "1") (pinfunction "1_1") (pintype "passive"))
      (node (ref "C7") (pin "2") (pinfunction "2_2") (pintype "passive"))
      (node (ref "D3") (pin "A") (pinfunction "A_A") (pintype "passive"))
      (node (ref "ICSP") (pin "5") (pinfunction "5_5") (pintype "passive"))
      (node (ref "R4") (pin "1") (pinfunction "1_1") (pintype "passive"))
      (node (ref "RESET") (pin "1") (pinfunction "P_1") (pintype "passive"))
    )
    (net (code "81") (name "/RESET2") (class "Default")
      (node (ref "D2") (pin "A") (pinfunction "A_A") (pintype "passive"))
      (node (ref "IC4") (pin "24") (pinfunction "RESET(PC1/DW)_24") (pintype "input"))
      (node (ref "ICSP1") (pin "5") (pinfunction "5_5") (pintype "passive"))
      (node (ref "R3") (pin "1") (pinfunction "1_1") (pintype "passive"))
    )
    (net (code "82") (name "/RXL") (class "Default")
      (node (ref "IC4") (pin "10") (pinfunction "(INT5/AIN3)PD4_10") (pintype "bidirectional"))
      (node (ref "RX") (pin "C") (pinfunction "C_C") (pintype "passive"))
    )
    (net (code "83") (name "/SCK") (class "Default")
      (node (ref "ATMEGA2560") (pin "20") (pinfunction "(SCK/PCINT1)PB1_20") (pintype "bidirectional"))
      (node (ref "ICSP") (pin "3") (pinfunction "3_3") (pintype "passive"))
      (node (ref "U$1") (pin "CFG-2") (pinfunction "CFG-2_CFG-2") (pintype "bidirectional"))
      (node (ref "U$2") (pin "CFG-2") (pinfunction "CFG-2_CFG-2") (pintype "bidirectional"))
      (node (ref "U$3") (pin "CFG-2") (pinfunction "CFG-2_CFG-2") (pintype "bidirectional"))
      (node (ref "U$4") (pin "CFG-2") (pinfunction "CFG-2_CFG-2") (pintype "bidirectional"))
      (node (ref "U$5") (pin "CFG-2") (pinfunction "CFG-2_CFG-2") (pintype "bidirectional"))
    )
    (net (code "84") (name "/SCK2") (class "Default")
      (node (ref "IC4") (pin "15") (pinfunction "(SCLK/PCINT1)PB1_15") (pintype "bidirectional"))
      (node (ref "ICSP1") (pin "3") (pinfunction "3_3") (pintype "passive"))
    )
    (net (code "85") (name "/SCL") (class "Default")
      (node (ref "ATMEGA2560") (pin "43") (pinfunction "(SCL/INT0)PD0_43") (pintype "bidirectional"))
      (node (ref "I2C") (pin "4") (pinfunction "4_4") (pintype "passive"))
      (node (ref "R12") (pin "1") (pinfunction "1_1") (pintype "passive"))
    )
    (net (code "86") (name "/SDA") (class "Default")
      (node (ref "ATMEGA2560") (pin "44") (pinfunction "(SDA/INT1)PD1_44") (pintype "bidirectional"))
      (node (ref "I2C") (pin "3") (pinfunction "3_3") (pintype "passive"))
      (node (ref "R11") (pin "1") (pinfunction "1_1") (pintype "passive"))
    )
    (net (code "87") (name "/TXL") (class "Default")
      (node (ref "IC4") (pin "11") (pinfunction "(XCK/AIN4/PCINT12)PD5_11") (pintype "bidirectional"))
      (node (ref "TX") (pin "C") (pinfunction "C_C") (pintype "passive"))
    )
    (net (code "88") (name "/UGND") (class "Default")
      (node (ref "C10") (pin "2") (pinfunction "2_2") (pintype "passive"))
      (node (ref "GND") (pin "1") (pinfunction "1_1") (pintype "passive"))
      (node (ref "IC4") (pin "28") (pinfunction "UGND_28") (pintype "power_in"))
      (node (ref "L1") (pin "1") (pinfunction "1_1") (pintype "passive"))
      (node (ref "X2") (pin "4") (pinfunction "4_4") (pintype "bidirectional"))
    )
    (net (code "89") (name "/USBVCC") (class "Default")
      (node (ref "C8") (pin "1") (pinfunction "1_1") (pintype "passive"))
      (node (ref "IC4") (pin "31") (pinfunction "UVCC_31") (pintype "power_in"))
      (node (ref "X2") (pin "1") (pinfunction "1_1") (pintype "bidirectional"))
    )
    (net (code "90") (name "/USHIELD") (class "Default")
      (node (ref "L1") (pin "2") (pinfunction "2_2") (pintype "passive"))
      (node (ref "X2") (pin "P$1") (pinfunction "P$1_P$1") (pintype "bidirectional"))
      (node (ref "X2") (pin "P$2") (pinfunction "P$2_P$2") (pintype "bidirectional"))
      (node (ref "Z1") (pin "1") (pinfunction "1_1") (pintype "passive"))
      (node (ref "Z2") (pin "1") (pinfunction "1_1") (pintype "passive"))
    )
    (net (code "91") (name "/VIN") (class "Default")
      (node (ref "C2") (pin "1") (pinfunction "1_1") (pintype "passive"))
      (node (ref "D4") (pin "C") (pinfunction "C_C") (pintype "passive"))
      (node (ref "IC1") (pin "3") (pinfunction "IN_3") (pintype "input"))
      (node (ref "PC1") (pin "+") (pinfunction "+_+") (pintype "passive"))
    )
    (net (code "92") (name "/VUCAP") (class "Default")
      (node (ref "C10") (pin "1") (pinfunction "1_1") (pintype "passive"))
      (node (ref "IC4") (pin "27") (pinfunction "UCAP_27") (pintype "passive"))
    )
    (net (code "93") (name "/XT1") (class "Default")
      (node (ref "C14") (pin "1") (pinfunction "1_1") (pintype "passive"))
      (node (ref "IC4") (pin "1") (pinfunction "XTAL1_1") (pintype "bidirectional"))
      (node (ref "R2") (pin "1") (pinfunction "1_1") (pintype "passive"))
      (node (ref "Y2") (pin "2") (pinfunction "2_2") (pintype "passive"))
    )
    (net (code "94") (name "/XT2") (class "Default")
      (node (ref "C15") (pin "1") (pinfunction "1_1") (pintype "passive"))
      (node (ref "IC4") (pin "2") (pinfunction "XTAL2(PC0)_2") (pintype "bidirectional"))
      (node (ref "R2") (pin "2") (pinfunction "2_2") (pintype "passive"))
      (node (ref "Y2") (pin "1") (pinfunction "1_1") (pintype "passive"))
    )
    (net (code "95") (name "/XTAL1") (class "Default")
      (node (ref "ATMEGA2560") (pin "34") (pinfunction "XTAL1_34") (pintype "input"))
      (node (ref "R1") (pin "1") (pinfunction "1_1") (pintype "passive"))
      (node (ref "Y1") (pin "3") (pinfunction "3_3") (pintype "passive"))
    )
    (net (code "96") (name "/XTAL2") (class "Default")
      (node (ref "ATMEGA2560") (pin "33") (pinfunction "XTAL2_33") (pintype "output"))
      (node (ref "R1") (pin "2") (pinfunction "2_2") (pintype "passive"))
      (node (ref "Y1") (pin "1") (pinfunction "1_1") (pintype "passive"))
    )
    (net (code "97") (name "GND") (class "Default")
      (node (ref "A-OUT") (pin "2") (pinfunction "2_2") (pintype "passive"))
      (node (ref "ATMEGA2560") (pin "11") (pinfunction "GND_11") (pintype "power_in"))
      (node (ref "ATMEGA2560") (pin "32") (pinfunction "GND1_32") (pintype "power_in"))
      (node (ref "ATMEGA2560") (pin "62") (pinfunction "GND2_62") (pintype "power_in"))
      (node (ref "ATMEGA2560") (pin "81") (pinfunction "GND3_81") (pintype "power_in"))
      (node (ref "ATMEGA2560") (pin "99") (pinfunction "AGND_99") (pintype "power_in"))
      (node (ref "AUX-4") (pin "23") (pinfunction "23_23") (pintype "passive"))
      (node (ref "AUX-4") (pin "24") (pinfunction "24_24") (pintype "passive"))
      (node (ref "AUX-4") (pin "3") (pinfunction "3_3") (pintype "passive"))
      (node (ref "AUX-4") (pin "4") (pinfunction "4_4") (pintype "passive"))
      (node (ref "C1") (pin "2") (pinfunction "2_2") (pintype "passive"))
      (node (ref "C11") (pin "2") (pinfunction "2_2") (pintype "passive"))
      (node (ref "C12") (pin "-") (pinfunction "-_-") (pintype "passive"))
      (node (ref "C13") (pin "2") (pinfunction "2_2") (pintype "passive"))
      (node (ref "C14") (pin "2") (pinfunction "2_2") (pintype "passive"))
      (node (ref "C15") (pin "2") (pinfunction "2_2") (pintype "passive"))
      (node (ref "C2") (pin "2") (pinfunction "2_2") (pintype "passive"))
      (node (ref "C20") (pin "2") (pinfunction "2_2") (pintype "passive"))
      (node (ref "C21") (pin "-") (pinfunction "-_-") (pintype "passive"))
      (node (ref "C22") (pin "-") (pinfunction "-_-") (pintype "passive"))
      (node (ref "C23") (pin "-") (pinfunction "-_-") (pintype "passive"))
      (node (ref "C24") (pin "-") (pinfunction "-_-") (pintype "passive"))
      (node (ref "C25") (pin "-") (pinfunction "-_-") (pintype "passive"))
      (node (ref "C4") (pin "2") (pinfunction "2_2") (pintype "passive"))
      (node (ref "C40") (pin "-") (pinfunction "-_-") (pintype "passive"))
      (node (ref "C41") (pin "-") (pinfunction "-_-") (pintype "passive"))
      (node (ref "C42") (pin "-") (pinfunction "-_-") (pintype "passive"))
      (node (ref "C43") (pin "-") (pinfunction "-_-") (pintype "passive"))
      (node (ref "C5") (pin "2") (pinfunction "2_2") (pintype "passive"))
      (node (ref "C6") (pin "2") (pinfunction "2_2") (pintype "passive"))
      (node (ref "C8") (pin "2") (pinfunction "2_2") (pintype "passive"))
      (node (ref "C9") (pin "2") (pinfunction "2_2") (pintype "passive"))
      (node (ref "D5") (pin "A") (pinfunction "A_A") (pintype "passive"))
      (node (ref "GND") (pin "2") (pinfunction "2_2") (pintype "passive"))
      (node (ref "I2C") (pin "2") (pinfunction "2_2") (pintype "passive"))
      (node (ref "IC1") (pin "1") (pinfunction "GND/ADJ_1") (pintype "input"))
      (node (ref "IC4") (pin "3") (pinfunction "GND_3") (pintype "power_in"))
      (node (ref "IC4") (pin "33") (pinfunction "PAD_33") (pintype "power_in"))
      (node (ref "ICSP") (pin "6") (pinfunction "6_6") (pintype "passive"))
      (node (ref "ICSP1") (pin "6") (pinfunction "6_6") (pintype "passive"))
      (node (ref "J1") (pin "2") (pinfunction "2_2") (pintype "passive"))
      (node (ref "J2") (pin "1") (pinfunction "1_1") (pintype "passive"))
      (node (ref "J3") (pin "1") (pinfunction "1_1") (pintype "passive"))
      (node (ref "J4") (pin "1") (pinfunction "1_1") (pintype "passive"))
      (node (ref "J5") (pin "1") (pinfunction "1_1") (pintype "passive"))
      (node (ref "JP7") (pin "1") (pinfunction "1_1") (pintype "passive"))
      (node (ref "JP7") (pin "3") (pinfunction "3_3") (pintype "passive"))
      (node (ref "JP7") (pin "5") (pinfunction "5_5") (pintype "passive"))
      (node (ref "JP7") (pin "7") (pinfunction "7_7") (pintype "passive"))
      (node (ref "L") (pin "C") (pinfunction "C_C") (pintype "passive"))
      (node (ref "ON") (pin "C") (pinfunction "C_C") (pintype "passive"))
      (node (ref "P1") (pin "3") (pinfunction "CW_3") (pintype "bidirectional"))
      (node (ref "PC1") (pin "-") (pinfunction "-_-") (pintype "passive"))
      (node (ref "PC2") (pin "-") (pinfunction "-_-") (pintype "passive"))
      (node (ref "Q1") (pin "S") (pinfunction "S_S") (pintype "passive"))
      (node (ref "Q2") (pin "S") (pinfunction "S_S") (pintype "passive"))
      (node (ref "Q3") (pin "1") (pinfunction "S_1") (pintype "passive"))
      (node (ref "Q3") (pin "3") (pinfunction "S_3") (pintype "passive"))
      (node (ref "Q4") (pin "1") (pinfunction "S_1") (pintype "passive"))
      (node (ref "Q4") (pin "3") (pinfunction "S_3") (pintype "passive"))
      (node (ref "R21") (pin "1") (pinfunction "1_1") (pintype "passive"))
      (node (ref "R61") (pin "2") (pinfunction "2_2") (pintype "passive"))
      (node (ref "R62") (pin "2") (pinfunction "2_2") (pintype "passive"))
      (node (ref "R66") (pin "2") (pinfunction "2_2") (pintype "passive"))
      (node (ref "R67") (pin "2") (pinfunction "2_2") (pintype "passive"))
      (node (ref "R68") (pin "2") (pinfunction "2_2") (pintype "passive"))
      (node (ref "R69") (pin "2") (pinfunction "2_2") (pintype "passive"))
      (node (ref "RESET") (pin "2") (pinfunction "S_2") (pintype "passive"))
      (node (ref "RN4") (pin "5") (pinfunction "2_5") (pintype "passive"))
      (node (ref "SERIAL") (pin "2") (pinfunction "2_2") (pintype "passive"))
      (node (ref "U$1") (pin "GND") (pinfunction "GND_GND") (pintype "power_in"))
      (node (ref "U$1") (pin "GND@0") (pinfunction "GND_GND@0") (pintype "power_in"))
      (node (ref "U$2") (pin "GND") (pinfunction "GND_GND") (pintype "power_in"))
      (node (ref "U$2") (pin "GND@0") (pinfunction "GND_GND@0") (pintype "power_in"))
      (node (ref "U$3") (pin "GND") (pinfunction "GND_GND") (pintype "power_in"))
      (node (ref "U$3") (pin "GND@0") (pinfunction "GND_GND@0") (pintype "power_in"))
      (node (ref "U$4") (pin "GND") (pinfunction "GND_GND") (pintype "power_in"))
      (node (ref "U$4") (pin "GND@0") (pinfunction "GND_GND@0") (pintype "power_in"))
      (node (ref "U$5") (pin "GND") (pinfunction "GND_GND") (pintype "power_in"))
      (node (ref "U$5") (pin "GND@0") (pinfunction "GND_GND@0") (pintype "power_in"))
      (node (ref "X+") (pin "2") (pinfunction "2_2") (pintype "passive"))
      (node (ref "X-") (pin "2") (pinfunction "2_2") (pintype "passive"))
      (node (ref "X1") (pin "P$2") (pinfunction "1_P$2") (pintype "passive"))
      (node (ref "Y+") (pin "2") (pinfunction "2_2") (pintype "passive"))
      (node (ref "Y-") (pin "2") (pinfunction "2_2") (pintype "passive"))
      (node (ref "Y1") (pin "2") (pinfunction "2_2") (pintype "passive"))
      (node (ref "Z+") (pin "2") (pinfunction "2_2") (pintype "passive"))
      (node (ref "Z-") (pin "2") (pinfunction "2_2") (pintype "passive"))
      (node (ref "Z12V") (pin "2") (pinfunction "2_2") (pintype "passive"))
    )
    (net (code "98") (name "Net-(C20-Pad1)") (class "Default")
      (node (ref "C20") (pin "1") (pinfunction "1_1") (pintype "passive"))
      (node (ref "R21") (pin "2") (pinfunction "2_2") (pintype "passive"))
      (node (ref "R22") (pin "2") (pinfunction "2_2") (pintype "passive"))
      (node (ref "Z12V") (pin "1") (pinfunction "1_1") (pintype "passive"))
    )
    (net (code "99") (name "Net-(FANS-Pad2)") (class "Default")
      (node (ref "FANS") (pin "2") (pinfunction "2_2") (pintype "passive"))
      (node (ref "L6") (pin "C") (pinfunction "C_C") (pintype "passive"))
      (node (ref "Q3") (pin "5") (pinfunction "D_5") (pintype "passive"))
      (node (ref "Q3") (pin "6") (pinfunction "D_6") (pintype "passive"))
    )
    (net (code "100") (name "Net-(FANS-Pad4)") (class "Default")
      (node (ref "FANS") (pin "4") (pinfunction "4_4") (pintype "passive"))
      (node (ref "L7") (pin "C") (pinfunction "C_C") (pintype "passive"))
      (node (ref "Q3") (pin "7") (pinfunction "D_7") (pintype "passive"))
      (node (ref "Q3") (pin "8") (pinfunction "D_8") (pintype "passive"))
    )
    (net (code "101") (name "Net-(FANS-Pad6)") (class "Default")
      (node (ref "FANS") (pin "6") (pinfunction "6_6") (pintype "passive"))
      (node (ref "L8") (pin "C") (pinfunction "C_C") (pintype "passive"))
      (node (ref "Q4") (pin "5") (pinfunction "D_5") (pintype "passive"))
      (node (ref "Q4") (pin "6") (pinfunction "D_6") (pintype "passive"))
    )
    (net (code "102") (name "Net-(FANS-Pad8)") (class "Default")
      (node (ref "FANS") (pin "8") (pinfunction "8_8") (pintype "passive"))
      (node (ref "L9") (pin "C") (pinfunction "C_C") (pintype "passive"))
      (node (ref "Q4") (pin "7") (pinfunction "D_7") (pintype "passive"))
      (node (ref "Q4") (pin "8") (pinfunction "D_8") (pintype "passive"))
    )
    (net (code "103") (name "Net-(L-PadA)") (class "Default")
      (node (ref "L") (pin "A") (pinfunction "A_A") (pintype "passive"))
      (node (ref "RN3") (pin "1") (pinfunction "1_1") (pintype "passive"))
    )
    (net (code "104") (name "Net-(L6-PadA)") (class "Default")
      (node (ref "L6") (pin "A") (pinfunction "A_A") (pintype "passive"))
      (node (ref "R76") (pin "1") (pinfunction "1_1") (pintype "passive"))
    )
    (net (code "105") (name "Net-(L7-PadA)") (class "Default")
      (node (ref "L7") (pin "A") (pinfunction "A_A") (pintype "passive"))
      (node (ref "R77") (pin "1") (pinfunction "1_1") (pintype "passive"))
    )
    (net (code "106") (name "Net-(L8-PadA)") (class "Default")
      (node (ref "L8") (pin "A") (pinfunction "A_A") (pintype "passive"))
      (node (ref "R78") (pin "1") (pinfunction "1_1") (pintype "passive"))
    )
    (net (code "107") (name "Net-(L9-PadA)") (class "Default")
      (node (ref "L9") (pin "A") (pinfunction "A_A") (pintype "passive"))
      (node (ref "R79") (pin "1") (pinfunction "1_1") (pintype "passive"))
    )
    (net (code "108") (name "Net-(L11-PadA)") (class "Default")
      (node (ref "L11") (pin "A") (pinfunction "A_A") (pintype "passive"))
      (node (ref "R71") (pin "2") (pinfunction "2_2") (pintype "passive"))
    )
    (net (code "109") (name "Net-(L11-PadC)") (class "Default")
      (node (ref "L11") (pin "C") (pinfunction "C_C") (pintype "passive"))
      (node (ref "Q1") (pin "D") (pinfunction "D_D") (pintype "passive"))
      (node (ref "X3") (pin "1") (pinfunction "1_1") (pintype "passive"))
    )
    (net (code "110") (name "Net-(L12-PadA)") (class "Default")
      (node (ref "L12") (pin "A") (pinfunction "A_A") (pintype "passive"))
      (node (ref "R72") (pin "2") (pinfunction "2_2") (pintype "passive"))
    )
    (net (code "111") (name "Net-(Q1-PadG)") (class "Default")
      (node (ref "Q1") (pin "G") (pinfunction "G_G") (pintype "passive"))
      (node (ref "R51") (pin "2") (pinfunction "2_2") (pintype "passive"))
    )
    (net (code "112") (name "Net-(Q2-PadG)") (class "Default")
      (node (ref "Q2") (pin "G") (pinfunction "G_G") (pintype "passive"))
      (node (ref "R52") (pin "2") (pinfunction "2_2") (pintype "passive"))
    )
    (net (code "113") (name "Net-(Q3A-G)") (class "Default")
      (node (ref "Q3") (pin "2") (pinfunction "G_2") (pintype "passive"))
      (node (ref "R57") (pin "2") (pinfunction "2_2") (pintype "passive"))
    )
    (net (code "114") (name "Net-(Q3B-G)") (class "Default")
      (node (ref "Q3") (pin "4") (pinfunction "G_4") (pintype "passive"))
      (node (ref "R56") (pin "2") (pinfunction "2_2") (pintype "passive"))
    )
    (net (code "115") (name "Net-(Q4A-G)") (class "Default")
      (node (ref "Q4") (pin "2") (pinfunction "G_2") (pintype "passive"))
      (node (ref "R59") (pin "2") (pinfunction "2_2") (pintype "passive"))
    )
    (net (code "116") (name "Net-(Q4B-G)") (class "Default")
      (node (ref "Q4") (pin "4") (pinfunction "G_4") (pintype "passive"))
      (node (ref "R58") (pin "2") (pinfunction "2_2") (pintype "passive"))
    )
    (net (code "117") (name "Net-(RN3B-2)") (class "Default")
      (node (ref "ON") (pin "A") (pinfunction "A_A") (pintype "passive"))
      (node (ref "RN3") (pin "7") (pinfunction "2_7") (pintype "passive"))
    )
    (net (code "118") (name "Net-(RN3C-2)") (class "Default")
      (node (ref "RN3") (pin "6") (pinfunction "2_6") (pintype "passive"))
      (node (ref "RX") (pin "A") (pinfunction "A_A") (pintype "passive"))
    )
    (net (code "119") (name "Net-(RN3D-2)") (class "Default")
      (node (ref "RN3") (pin "5") (pinfunction "2_5") (pintype "passive"))
      (node (ref "TX") (pin "A") (pinfunction "A_A") (pintype "passive"))
    )
    (net (code "120") (name "Net-(U$1-O1A)") (class "Default")
      (node (ref "U$1") (pin "OA1") (pinfunction "O1A_OA1") (pintype "output"))
      (node (ref "X-MOT") (pin "3") (pinfunction "3_3") (pintype "passive"))
    )
    (net (code "121") (name "Net-(U$1-O1B)") (class "Default")
      (node (ref "U$1") (pin "OA2") (pinfunction "O1B_OA2") (pintype "output"))
      (node (ref "X-MOT") (pin "4") (pinfunction "4_4") (pintype "passive"))
    )
    (net (code "122") (name "Net-(U$1-O2A)") (class "Default")
      (node (ref "U$1") (pin "OB1") (pinfunction "O2A_OB1") (pintype "output"))
      (node (ref "X-MOT") (pin "2") (pinfunction "2_2") (pintype "passive"))
    )
    (net (code "123") (name "Net-(U$1-O2B)") (class "Default")
      (node (ref "U$1") (pin "OB2") (pinfunction "O2B_OB2") (pintype "output"))
      (node (ref "X-MOT") (pin "1") (pinfunction "1_1") (pintype "passive"))
    )
    (net (code "124") (name "Net-(U$2-O1A)") (class "Default")
      (node (ref "U$2") (pin "OA1") (pinfunction "O1A_OA1") (pintype "output"))
      (node (ref "Y-MOT") (pin "3") (pinfunction "3_3") (pintype "passive"))
    )
    (net (code "125") (name "Net-(U$2-O1B)") (class "Default")
      (node (ref "U$2") (pin "OA2") (pinfunction "O1B_OA2") (pintype "output"))
      (node (ref "Y-MOT") (pin "4") (pinfunction "4_4") (pintype "passive"))
    )
    (net (code "126") (name "Net-(U$2-O2A)") (class "Default")
      (node (ref "U$2") (pin "OB1") (pinfunction "O2A_OB1") (pintype "output"))
      (node (ref "Y-MOT") (pin "2") (pinfunction "2_2") (pintype "passive"))
    )
    (net (code "127") (name "Net-(U$2-O2B)") (class "Default")
      (node (ref "U$2") (pin "OB2") (pinfunction "O2B_OB2") (pintype "output"))
      (node (ref "Y-MOT") (pin "1") (pinfunction "1_1") (pintype "passive"))
    )
    (net (code "128") (name "Net-(U$3-O1A)") (class "Default")
      (node (ref "U$3") (pin "OA1") (pinfunction "O1A_OA1") (pintype "output"))
      (node (ref "Z-MOT") (pin "3") (pinfunction "3_3") (pintype "passive"))
      (node (ref "Z-MOT1") (pin "3") (pinfunction "3_3") (pintype "passive"))
    )
    (net (code "129") (name "Net-(U$3-O1B)") (class "Default")
      (node (ref "U$3") (pin "OA2") (pinfunction "O1B_OA2") (pintype "output"))
      (node (ref "Z-MOT") (pin "4") (pinfunction "4_4") (pintype "passive"))
      (node (ref "Z-MOT1") (pin "4") (pinfunction "4_4") (pintype "passive"))
    )
    (net (code "130") (name "Net-(U$3-O2A)") (class "Default")
      (node (ref "U$3") (pin "OB1") (pinfunction "O2A_OB1") (pintype "output"))
      (node (ref "Z-MOT") (pin "2") (pinfunction "2_2") (pintype "passive"))
      (node (ref "Z-MOT1") (pin "2") (pinfunction "2_2") (pintype "passive"))
    )
    (net (code "131") (name "Net-(U$3-O2B)") (class "Default")
      (node (ref "U$3") (pin "OB2") (pinfunction "O2B_OB2") (pintype "output"))
      (node (ref "Z-MOT") (pin "1") (pinfunction "1_1") (pintype "passive"))
      (node (ref "Z-MOT1") (pin "1") (pinfunction "1_1") (pintype "passive"))
    )
    (net (code "132") (name "Net-(U$4-O1A)") (class "Default")
      (node (ref "E1-MOT") (pin "3") (pinfunction "3_3") (pintype "passive"))
      (node (ref "U$4") (pin "OA1") (pinfunction "O1A_OA1") (pintype "output"))
    )
    (net (code "133") (name "Net-(U$4-O1B)") (class "Default")
      (node (ref "E1-MOT") (pin "4") (pinfunction "4_4") (pintype "passive"))
      (node (ref "U$4") (pin "OA2") (pinfunction "O1B_OA2") (pintype "output"))
    )
    (net (code "134") (name "Net-(U$4-O2A)") (class "Default")
      (node (ref "E1-MOT") (pin "2") (pinfunction "2_2") (pintype "passive"))
      (node (ref "U$4") (pin "OB1") (pinfunction "O2A_OB1") (pintype "output"))
    )
    (net (code "135") (name "Net-(U$4-O2B)") (class "Default")
      (node (ref "E1-MOT") (pin "1") (pinfunction "1_1") (pintype "passive"))
      (node (ref "U$4") (pin "OB2") (pinfunction "O2B_OB2") (pintype "output"))
    )
    (net (code "136") (name "Net-(U$5-O1A)") (class "Default")
      (node (ref "E0-MOT") (pin "3") (pinfunction "3_3") (pintype "passive"))
      (node (ref "U$5") (pin "OA1") (pinfunction "O1A_OA1") (pintype "output"))
    )
    (net (code "137") (name "Net-(U$5-O1B)") (class "Default")
      (node (ref "E0-MOT") (pin "4") (pinfunction "4_4") (pintype "passive"))
      (node (ref "U$5") (pin "OA2") (pinfunction "O1B_OA2") (pintype "output"))
    )
    (net (code "138") (name "Net-(U$5-O2A)") (class "Default")
      (node (ref "E0-MOT") (pin "2") (pinfunction "2_2") (pintype "passive"))
      (node (ref "U$5") (pin "OB1") (pinfunction "O2A_OB1") (pintype "output"))
    )
    (net (code "139") (name "Net-(U$5-O2B)") (class "Default")
      (node (ref "E0-MOT") (pin "1") (pinfunction "1_1") (pintype "passive"))
      (node (ref "U$5") (pin "OB2") (pinfunction "O2B_OB2") (pintype "output"))
    )
    (net (code "140") (name "Net-(X1A-1)") (class "Default")
      (node (ref "F1") (pin "2") (pinfunction "2_2") (pintype "passive"))
      (node (ref "X1") (pin "P$1") (pinfunction "1_P$1") (pintype "passive"))
    )
    (net (code "141") (name "Net-(X3C-1)") (class "Default")
      (node (ref "L12") (pin "C") (pinfunction "C_C") (pintype "passive"))
      (node (ref "Q2") (pin "D") (pinfunction "D_D") (pintype "passive"))
      (node (ref "X3") (pin "3") (pinfunction "1_3") (pintype "passive"))
    )
    (net (code "142") (name "unconnected-(ATMEGA2560-(CLKO{slash}ICP3{slash}INT7)PE7-Pad9)") (class "Default")
      (node (ref "ATMEGA2560") (pin "9") (pinfunction "(CLKO/ICP3/INT7)PE7_9") (pintype "bidirectional"))
    )
    (net (code "143") (name "unconnected-(ATMEGA2560-(ICP1)PD4-Pad47)") (class "Default")
      (node (ref "ATMEGA2560") (pin "47") (pinfunction "(ICP1)PD4_47") (pintype "bidirectional"))
    )
    (net (code "144") (name "unconnected-(ATMEGA2560-(T1)PD6-Pad49)") (class "Default")
      (node (ref "ATMEGA2560") (pin "49") (pinfunction "(T1)PD6_49") (pintype "bidirectional"))
    )
    (net (code "145") (name "unconnected-(ATMEGA2560-(T3{slash}INT6)PE6-Pad8)") (class "Default")
      (node (ref "ATMEGA2560") (pin "8") (pinfunction "(T3/INT6)PE6_8") (pintype "bidirectional"))
    )
    (net (code "146") (name "unconnected-(ATMEGA2560-(TOSC1)PG4-Pad29)") (class "Default")
      (node (ref "ATMEGA2560") (pin "29") (pinfunction "(TOSC1)PG4_29") (pintype "bidirectional"))
    )
    (net (code "147") (name "unconnected-(ATMEGA2560-(TOSC2)PG3-Pad28)") (class "Default")
      (node (ref "ATMEGA2560") (pin "28") (pinfunction "(TOSC2)PG3_28") (pintype "bidirectional"))
    )
    (net (code "148") (name "unconnected-(ATMEGA2560-(XCK0{slash}AIN0)PE2-Pad4)") (class "Default")
      (node (ref "ATMEGA2560") (pin "4") (pinfunction "(XCK0/AIN0)PE2_4") (pintype "bidirectional"))
    )
    (net (code "149") (name "unconnected-(ATMEGA2560-(XCK1)PD5-Pad48)") (class "Default")
      (node (ref "ATMEGA2560") (pin "48") (pinfunction "(XCK1)PD5_48") (pintype "bidirectional"))
    )
    (net (code "150") (name "unconnected-(ATMEGA2560-AREF-Pad98)") (class "Default")
      (node (ref "ATMEGA2560") (pin "98") (pinfunction "AREF_98") (pintype "bidirectional"))
    )
    (net (code "151") (name "unconnected-(ATMEGA2560-PH2(XCK2)-Pad14)") (class "Default")
      (node (ref "ATMEGA2560") (pin "14") (pinfunction "PH2(XCK2)_14") (pintype "bidirectional"))
    )
    (net (code "152") (name "unconnected-(ATMEGA2560-PH7(T4)-Pad27)") (class "Default")
      (node (ref "ATMEGA2560") (pin "27") (pinfunction "PH7(T4)_27") (pintype "bidirectional"))
    )
    (net (code "153") (name "unconnected-(ATMEGA2560-PJ2(XCK3{slash}PCINT11)-Pad65)") (class "Default")
      (node (ref "ATMEGA2560") (pin "65") (pinfunction "PJ2(XCK3/PCINT11)_65") (pintype "bidirectional"))
    )
    (net (code "154") (name "unconnected-(ATMEGA2560-PJ3(PCINT12)-Pad66)") (class "Default")
      (node (ref "ATMEGA2560") (pin "66") (pinfunction "PJ3(PCINT12)_66") (pintype "bidirectional"))
    )
    (net (code "155") (name "unconnected-(ATMEGA2560-PJ4(PCINT13)-Pad67)") (class "Default")
      (node (ref "ATMEGA2560") (pin "67") (pinfunction "PJ4(PCINT13)_67") (pintype "bidirectional"))
    )
    (net (code "156") (name "unconnected-(ATMEGA2560-PJ5(PCINT14)-Pad68)") (class "Default")
      (node (ref "ATMEGA2560") (pin "68") (pinfunction "PJ5(PCINT14)_68") (pintype "bidirectional"))
    )
    (net (code "157") (name "unconnected-(ATMEGA2560-PJ6(PCINT15)-Pad69)") (class "Default")
      (node (ref "ATMEGA2560") (pin "69") (pinfunction "PJ6(PCINT15)_69") (pintype "bidirectional"))
    )
    (net (code "158") (name "unconnected-(ATMEGA2560-PJ7-Pad79)") (class "Default")
      (node (ref "ATMEGA2560") (pin "79") (pinfunction "PJ7_79") (pintype "bidirectional"))
    )
    (net (code "159") (name "unconnected-(IC4-(AIN0{slash}INT1)PD1-Pad7)") (class "Default")
      (node (ref "IC4") (pin "7") (pinfunction "(AIN0/INT1)PD1_7") (pintype "bidirectional"))
    )
    (net (code "160") (name "unconnected-(IC4-(AIN2{slash}PCINT11)PC2-Pad5)") (class "Default")
      (node (ref "IC4") (pin "5") (pinfunction "(AIN2/PCINT11)PC2_5") (pintype "bidirectional"))
    )
    (net (code "161") (name "unconnected-(IC4-(INT4{slash}ICP1{slash}CLK0)PC7-Pad22)") (class "Default")
      (node (ref "IC4") (pin "22") (pinfunction "(INT4/ICP1/CLK0)PC7_22") (pintype "bidirectional"))
    )
    (net (code "162") (name "unconnected-(IC4-(OC0B{slash}INT0)PD0-Pad6)") (class "Default")
      (node (ref "IC4") (pin "6") (pinfunction "(OC0B/INT0)PD0_6") (pintype "bidirectional"))
    )
    (net (code "163") (name "unconnected-(IC4-(OC1A{slash}PCINT8)PC6-Pad23)") (class "Default")
      (node (ref "IC4") (pin "23") (pinfunction "(OC1A/PCINT8)PC6_23") (pintype "bidirectional"))
    )
    (net (code "164") (name "unconnected-(IC4-(PCINT5)PB5-Pad19)") (class "Default")
      (node (ref "IC4") (pin "19") (pinfunction "(PCINT5)PB5_19") (pintype "bidirectional"))
    )
    (net (code "165") (name "unconnected-(IC4-(PCINT6)PB6-Pad20)") (class "Default")
      (node (ref "IC4") (pin "20") (pinfunction "(PCINT6)PB6_20") (pintype "bidirectional"))
    )
    (net (code "166") (name "unconnected-(IC4-(PCINT7{slash}OC0A{slash}OC1C)PB7-Pad21)") (class "Default")
      (node (ref "IC4") (pin "21") (pinfunction "(PCINT7/OC0A/OC1C)PB7_21") (pintype "bidirectional"))
    )
    (net (code "167") (name "unconnected-(IC4-(PCINT9{slash}OC1B)PC5-Pad25)") (class "Default")
      (node (ref "IC4") (pin "25") (pinfunction "(PCINT9/OC1B)PC5_25") (pintype "bidirectional"))
    )
    (net (code "168") (name "unconnected-(IC4-(PCINT10)PC4-Pad26)") (class "Default")
      (node (ref "IC4") (pin "26") (pinfunction "(PCINT10)PC4_26") (pintype "bidirectional"))
    )
    (net (code "169") (name "unconnected-(IC4-(RTS{slash}AIN5{slash}INT6)PD6-Pad12)") (class "Default")
      (node (ref "IC4") (pin "12") (pinfunction "(RTS/AIN5/INT6)PD6_12") (pintype "bidirectional"))
    )
    (net (code "170") (name "unconnected-(IC4-(SS{slash}PCINT0)PB0-Pad14)") (class "Default")
      (node (ref "IC4") (pin "14") (pinfunction "(SS/PCINT0)PB0_14") (pintype "bidirectional"))
    )
    (net (code "171") (name "unconnected-(IC4-(T1{slash}PCINT4)PB4-Pad18)") (class "Default")
      (node (ref "IC4") (pin "18") (pinfunction "(T1/PCINT4)PB4_18") (pintype "bidirectional"))
    )
    (net (code "172") (name "unconnected-(RN4C-1-Pad3)") (class "Default")
      (node (ref "RN4") (pin "3") (pinfunction "1_3") (pintype "passive"))
    )
    (net (code "173") (name "unconnected-(RN4C-2-Pad6)") (class "Default")
      (node (ref "RN4") (pin "6") (pinfunction "2_6") (pintype "passive"))
    )
    (net (code "174") (name "unconnected-(U$1-PadIREF)") (class "Default")
      (node (ref "U$1") (pin "IREF") (pinfunction "IREF_IREF") (pintype "bidirectional"))
    )
    (net (code "175") (name "unconnected-(U$2-PadIREF)") (class "Default")
      (node (ref "U$2") (pin "IREF") (pinfunction "IREF_IREF") (pintype "bidirectional"))
    )
  )
)
